# CCM_0011_Subrack_Backplane.net
KiCad netlist of a schematic drawn in EAGLE
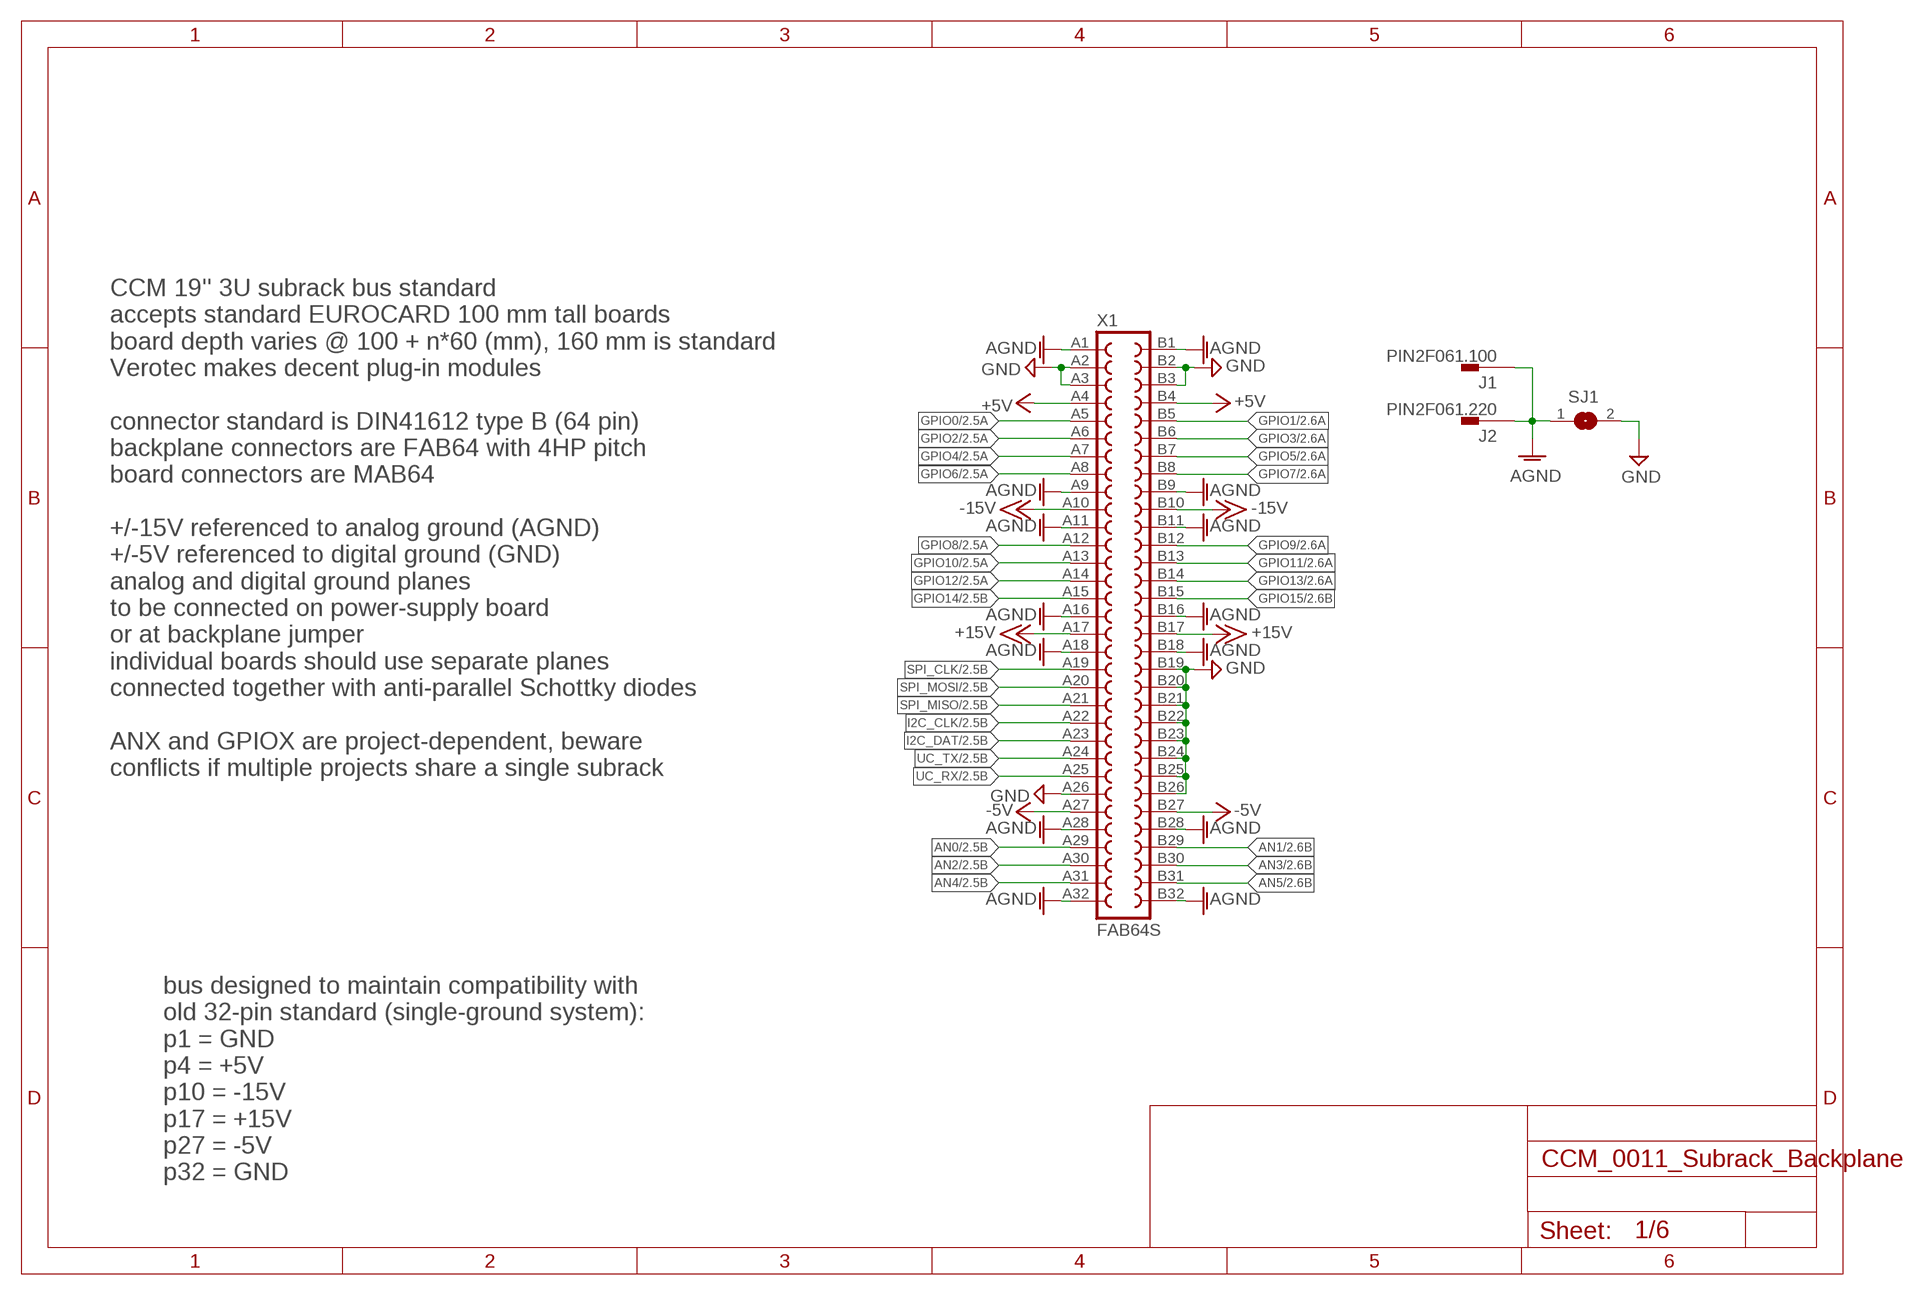
[diagram p0: schematic, sheet 1]
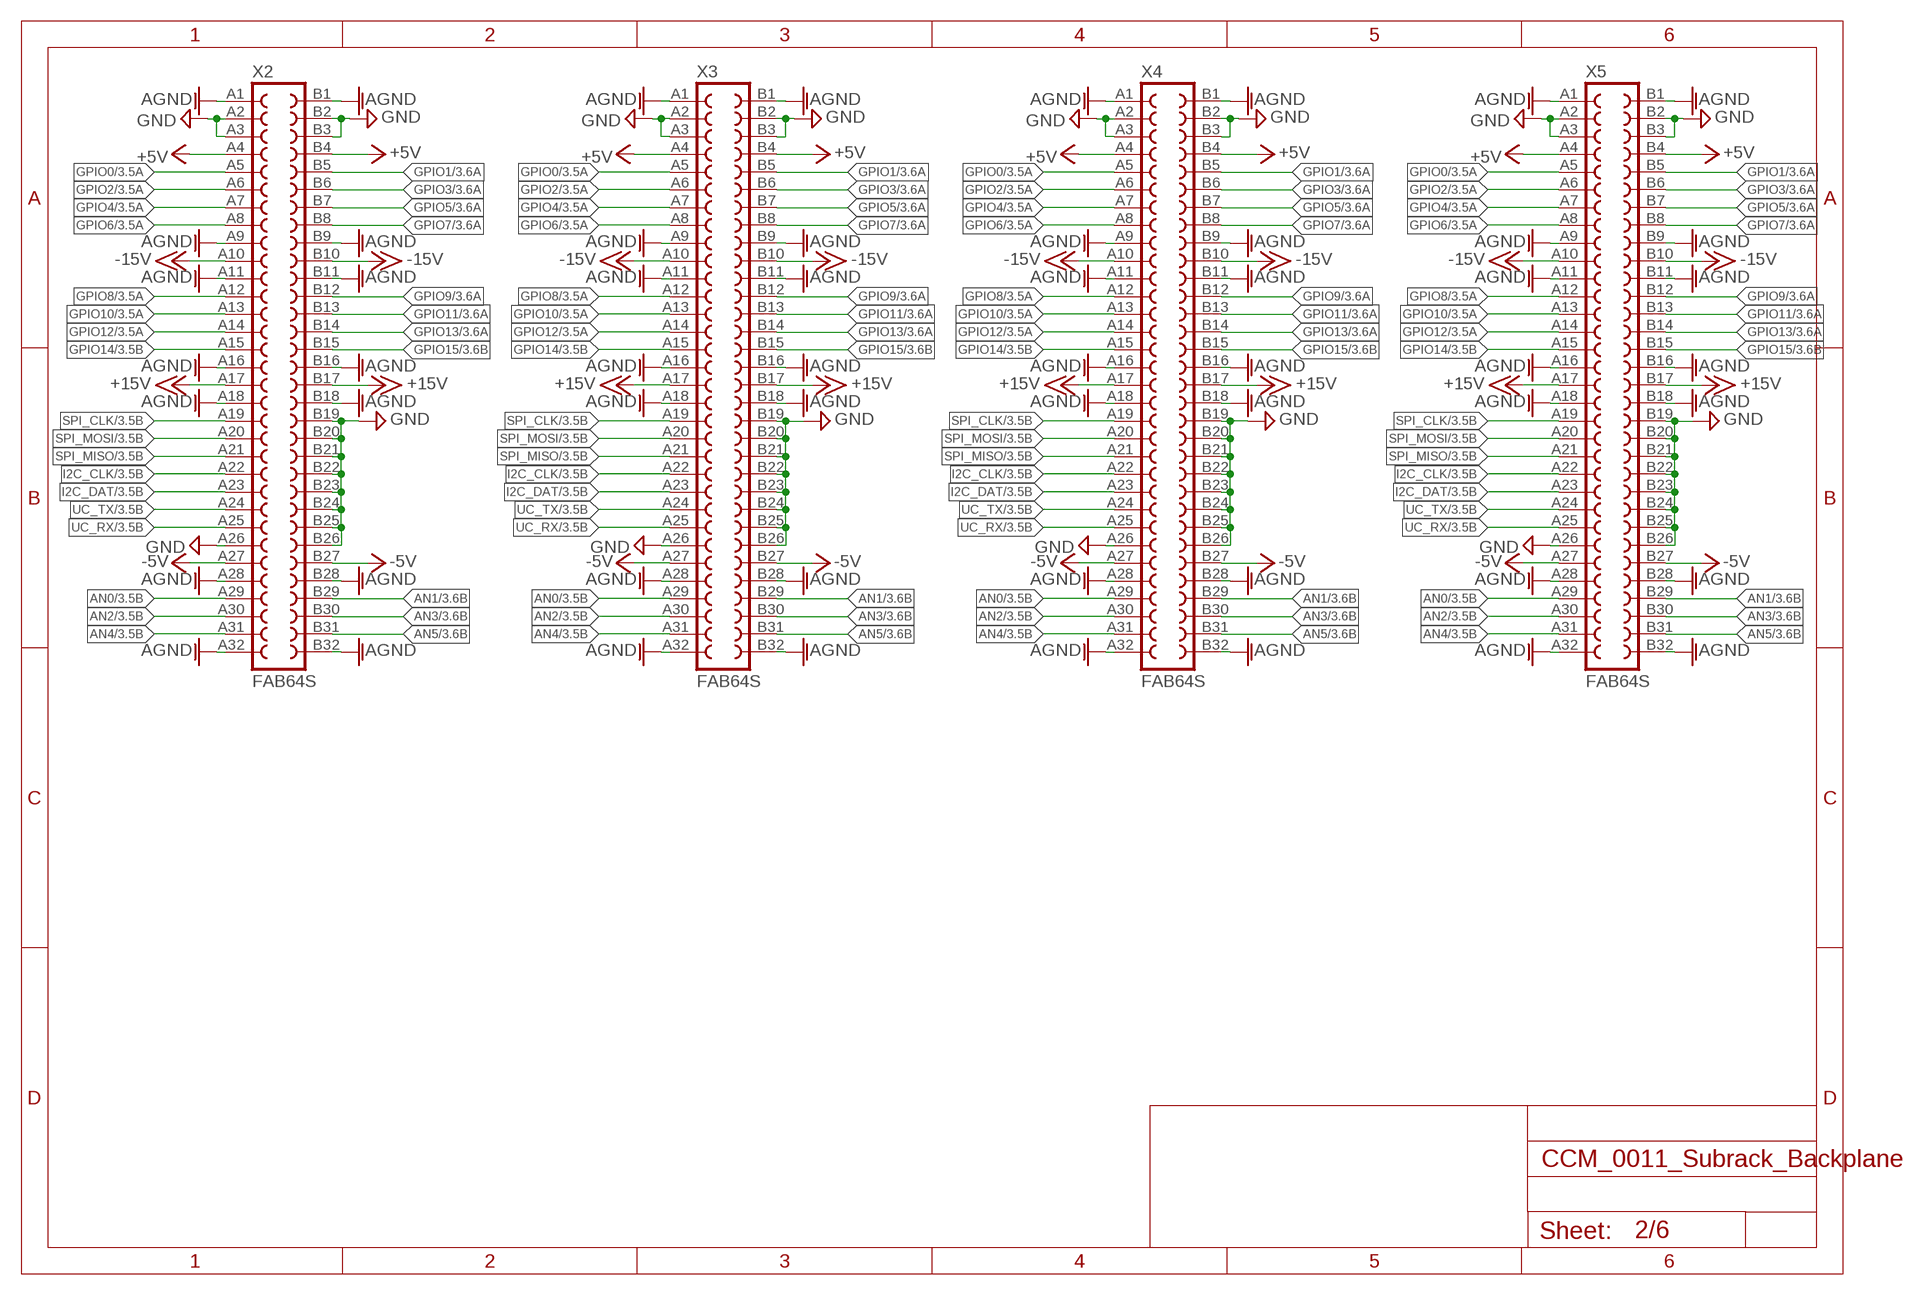
[diagram p1: schematic, sheet 2]
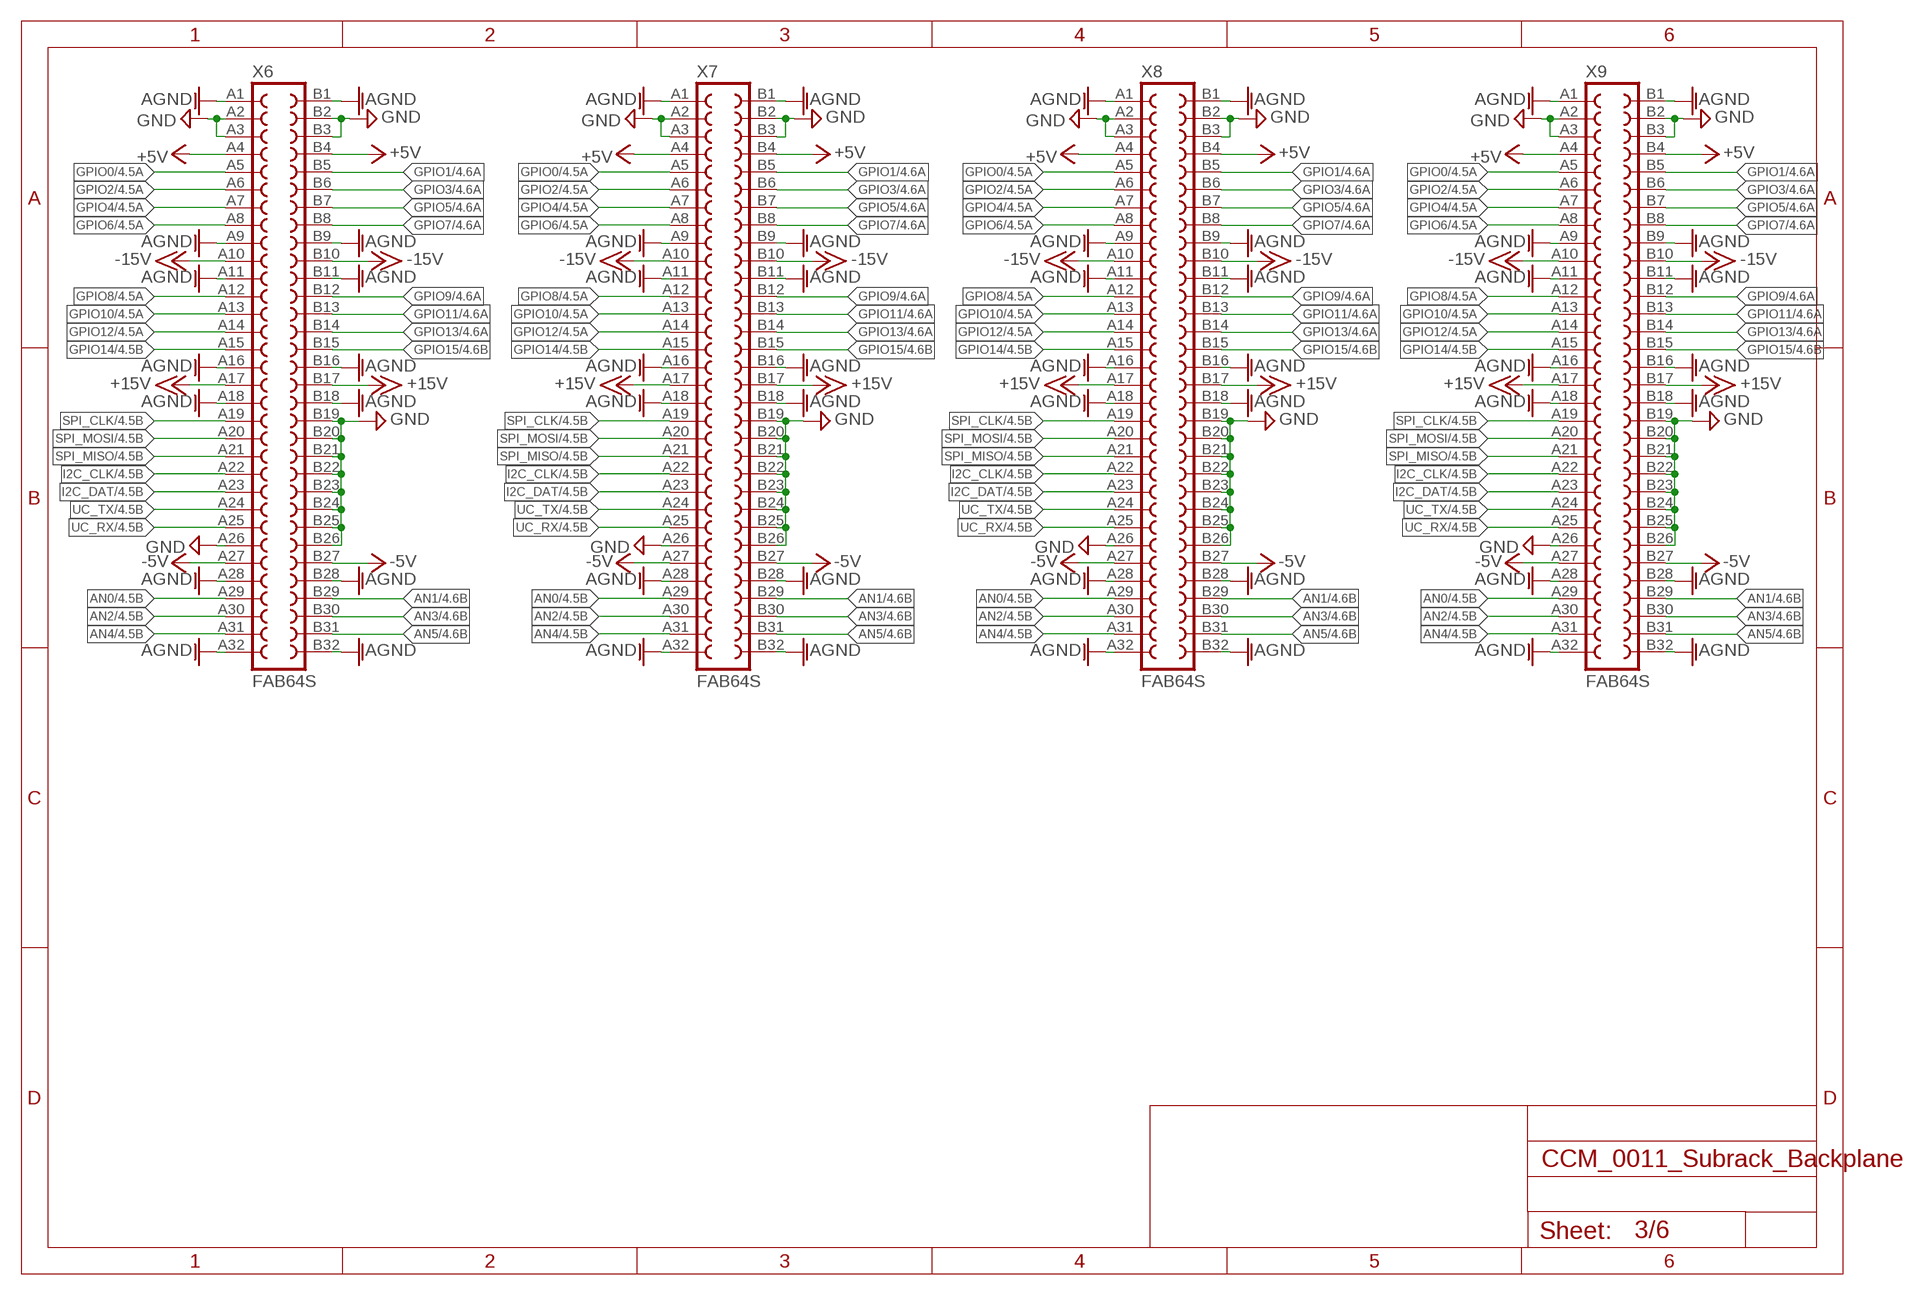
[diagram p2: schematic, sheet 3]
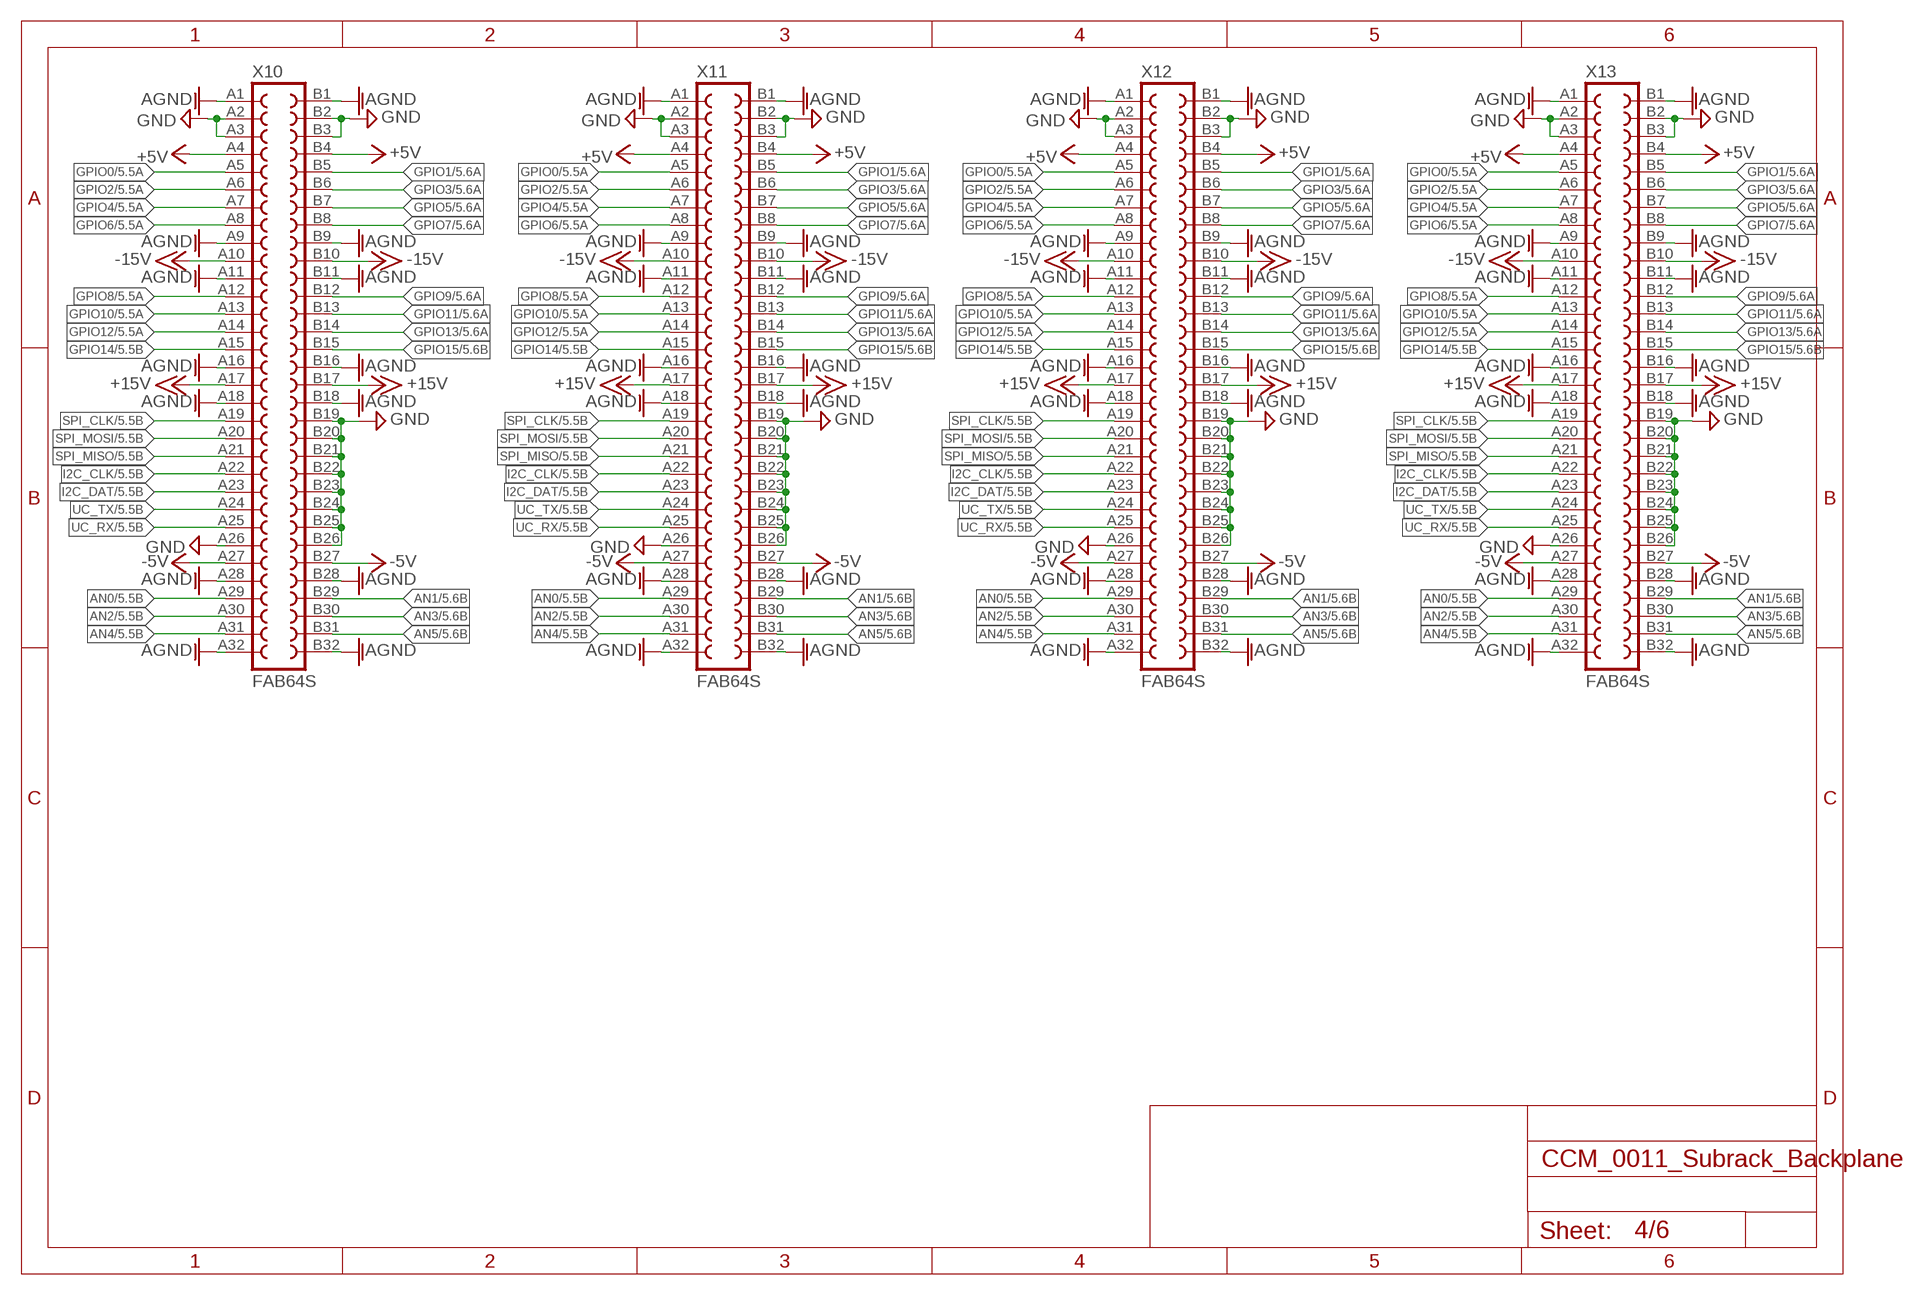
[diagram p3: schematic, sheet 4]
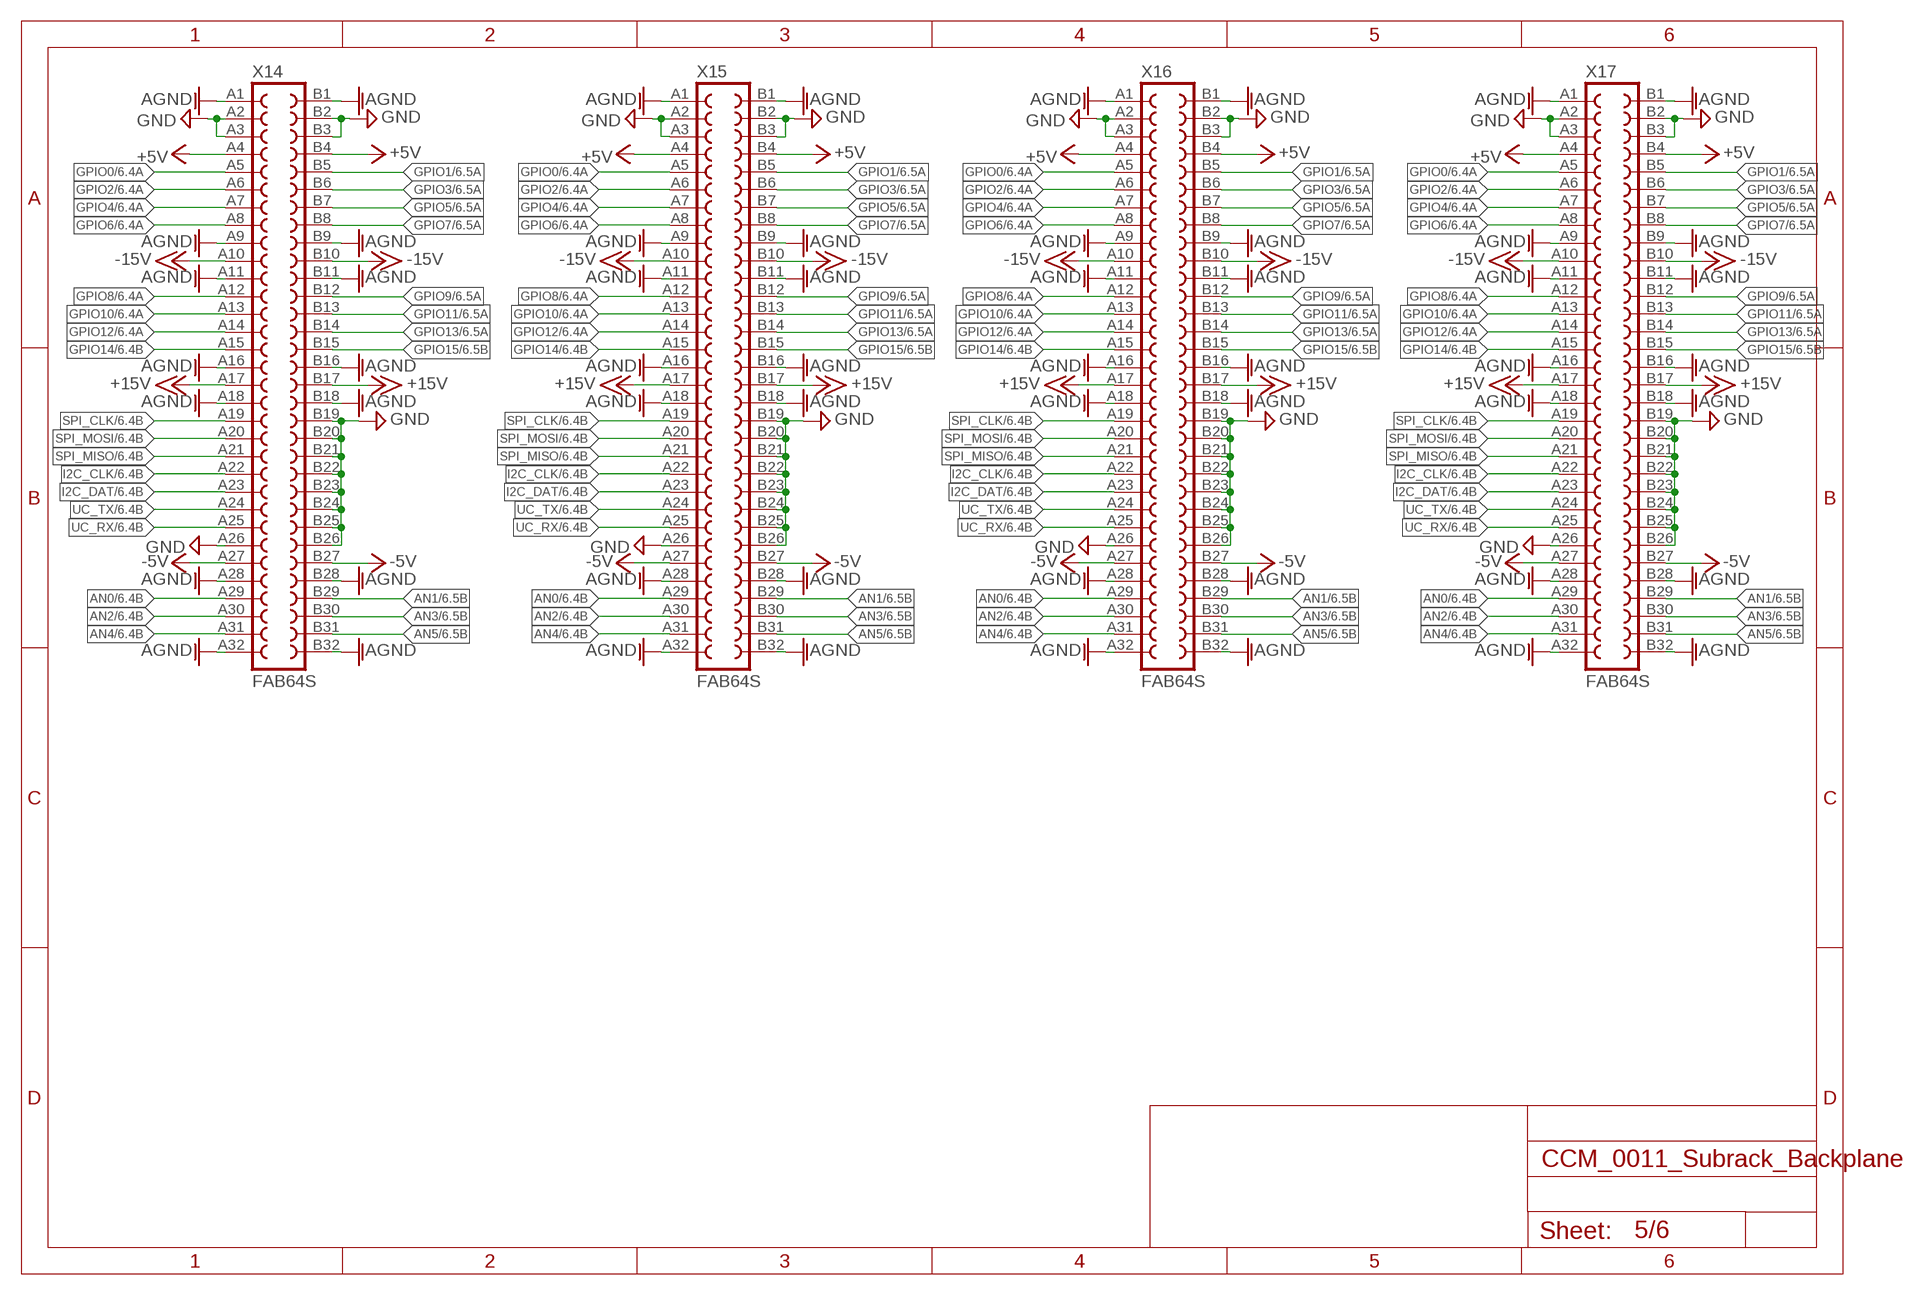
[diagram p4: schematic, sheet 5]
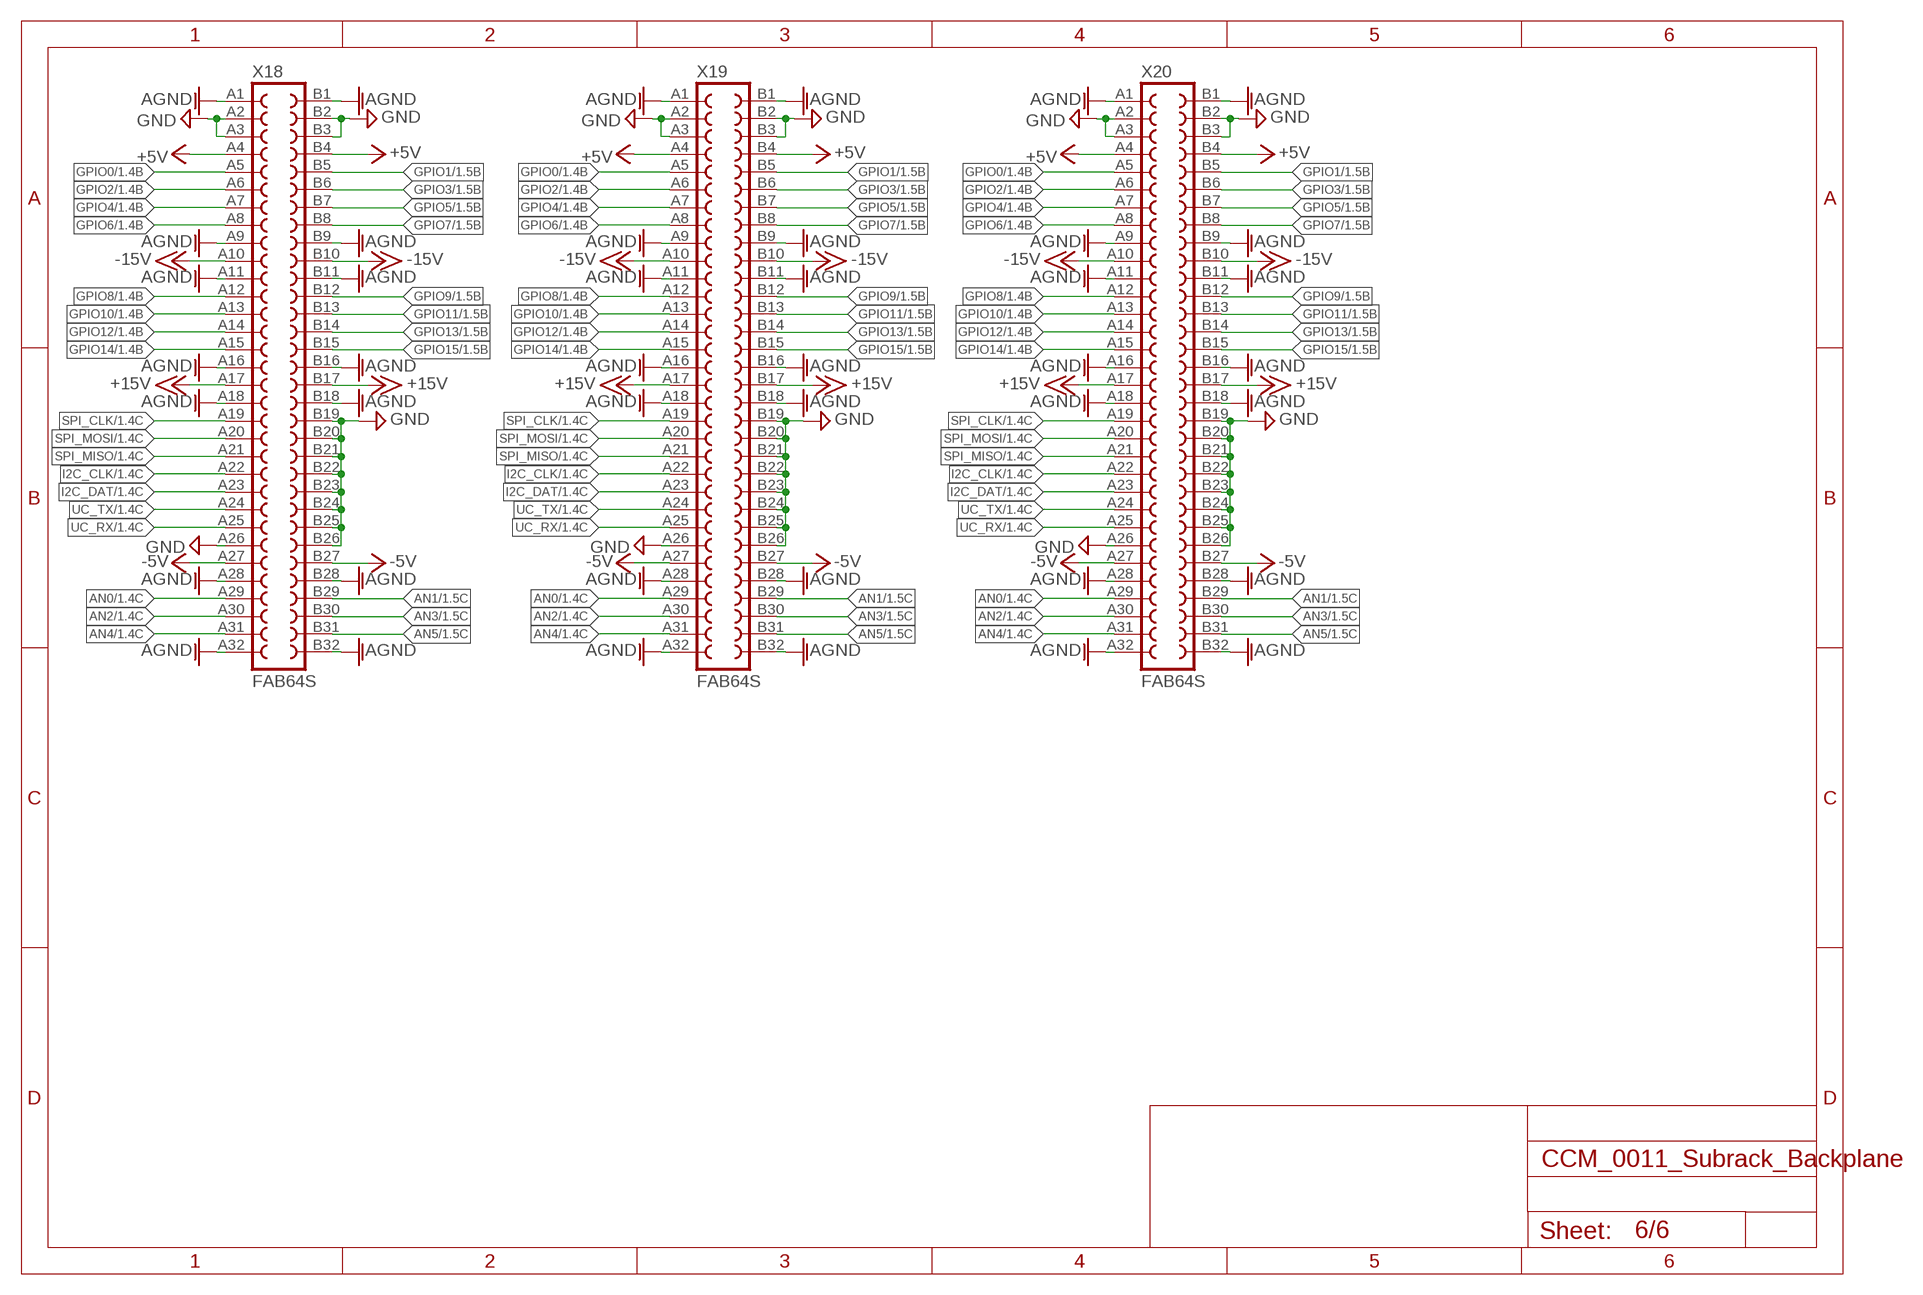
[diagram p5: schematic, sheet 6]

(export (version "E")
  (design (tool "Eeschema 10.0.6"))
  (components
    (comp (ref "X6")
      (value "FAB64S")
      (footprint "eagle-import:FAB64S")
      (libsource (lib "eagle-import") (part "FAB64S"))
    )
    (comp (ref "X7")
      (value "FAB64S")
      (footprint "eagle-import:FAB64S")
      (libsource (lib "eagle-import") (part "FAB64S"))
    )
    (comp (ref "X8")
      (value "FAB64S")
      (footprint "eagle-import:FAB64S")
      (libsource (lib "eagle-import") (part "FAB64S"))
    )
    (comp (ref "X9")
      (value "FAB64S")
      (footprint "eagle-import:FAB64S")
      (libsource (lib "eagle-import") (part "FAB64S"))
    )
    (comp (ref "X2")
      (value "FAB64S")
      (footprint "eagle-import:FAB64S")
      (libsource (lib "eagle-import") (part "FAB64S"))
    )
    (comp (ref "X3")
      (value "FAB64S")
      (footprint "eagle-import:FAB64S")
      (libsource (lib "eagle-import") (part "FAB64S"))
    )
    (comp (ref "X4")
      (value "FAB64S")
      (footprint "eagle-import:FAB64S")
      (libsource (lib "eagle-import") (part "FAB64S"))
    )
    (comp (ref "X5")
      (value "FAB64S")
      (footprint "eagle-import:FAB64S")
      (libsource (lib "eagle-import") (part "FAB64S"))
    )
    (comp (ref "J1")
      (value "PIN2F061.100")
      (footprint "eagle-import:F061.100")
      (libsource (lib "eagle-import") (part "PIN2F061.100"))
    )
    (comp (ref "J2")
      (value "PIN2F061.220")
      (footprint "eagle-import:F061.220")
      (libsource (lib "eagle-import") (part "PIN2F061.220"))
    )
    (comp (ref "SJ1") (value "SJ") (footprint "eagle-import:SJ") (libsource (lib "eagle-import") (part "SJ")))
    (comp (ref "X1")
      (value "FAB64S")
      (footprint "eagle-import:FAB64S")
      (libsource (lib "eagle-import") (part "noah_FAB64S"))
    )
    (comp (ref "X14")
      (value "FAB64S")
      (footprint "eagle-import:FAB64S")
      (libsource (lib "eagle-import") (part "FAB64S"))
    )
    (comp (ref "X15")
      (value "FAB64S")
      (footprint "eagle-import:FAB64S")
      (libsource (lib "eagle-import") (part "FAB64S"))
    )
    (comp (ref "X16")
      (value "FAB64S")
      (footprint "eagle-import:FAB64S")
      (libsource (lib "eagle-import") (part "FAB64S"))
    )
    (comp (ref "X17")
      (value "FAB64S")
      (footprint "eagle-import:FAB64S")
      (libsource (lib "eagle-import") (part "FAB64S"))
    )
    (comp (ref "X10")
      (value "FAB64S")
      (footprint "eagle-import:FAB64S")
      (libsource (lib "eagle-import") (part "FAB64S"))
    )
    (comp (ref "X11")
      (value "FAB64S")
      (footprint "eagle-import:FAB64S")
      (libsource (lib "eagle-import") (part "FAB64S"))
    )
    (comp (ref "X12")
      (value "FAB64S")
      (footprint "eagle-import:FAB64S")
      (libsource (lib "eagle-import") (part "FAB64S"))
    )
    (comp (ref "X13")
      (value "FAB64S")
      (footprint "eagle-import:FAB64S")
      (libsource (lib "eagle-import") (part "FAB64S"))
    )
    (comp (ref "X18")
      (value "FAB64S")
      (footprint "eagle-import:FAB64S")
      (libsource (lib "eagle-import") (part "FAB64S"))
    )
    (comp (ref "X19")
      (value "FAB64S")
      (footprint "eagle-import:FAB64S")
      (libsource (lib "eagle-import") (part "FAB64S"))
    )
    (comp (ref "X20")
      (value "FAB64S")
      (footprint "eagle-import:FAB64S")
      (libsource (lib "eagle-import") (part "FAB64S"))
    )
  )
  (nets
    (net (code "1") (name "+5V") (class "Default")
      (node (ref "X1") (pin "A4") (pinfunction "A4_A4") (pintype "passive"))
      (node (ref "X1") (pin "B4") (pinfunction "B4_B4") (pintype "passive"))
      (node (ref "X10") (pin "A4") (pinfunction "A4_A4") (pintype "passive"))
      (node (ref "X10") (pin "B4") (pinfunction "B4_B4") (pintype "passive"))
      (node (ref "X11") (pin "A4") (pinfunction "A4_A4") (pintype "passive"))
      (node (ref "X11") (pin "B4") (pinfunction "B4_B4") (pintype "passive"))
      (node (ref "X12") (pin "A4") (pinfunction "A4_A4") (pintype "passive"))
      (node (ref "X12") (pin "B4") (pinfunction "B4_B4") (pintype "passive"))
      (node (ref "X13") (pin "A4") (pinfunction "A4_A4") (pintype "passive"))
      (node (ref "X13") (pin "B4") (pinfunction "B4_B4") (pintype "passive"))
      (node (ref "X14") (pin "A4") (pinfunction "A4_A4") (pintype "passive"))
      (node (ref "X14") (pin "B4") (pinfunction "B4_B4") (pintype "passive"))
      (node (ref "X15") (pin "A4") (pinfunction "A4_A4") (pintype "passive"))
      (node (ref "X15") (pin "B4") (pinfunction "B4_B4") (pintype "passive"))
      (node (ref "X16") (pin "A4") (pinfunction "A4_A4") (pintype "passive"))
      (node (ref "X16") (pin "B4") (pinfunction "B4_B4") (pintype "passive"))
      (node (ref "X17") (pin "A4") (pinfunction "A4_A4") (pintype "passive"))
      (node (ref "X17") (pin "B4") (pinfunction "B4_B4") (pintype "passive"))
      (node (ref "X18") (pin "A4") (pinfunction "A4_A4") (pintype "passive"))
      (node (ref "X18") (pin "B4") (pinfunction "B4_B4") (pintype "passive"))
      (node (ref "X19") (pin "A4") (pinfunction "A4_A4") (pintype "passive"))
      (node (ref "X19") (pin "B4") (pinfunction "B4_B4") (pintype "passive"))
      (node (ref "X2") (pin "A4") (pinfunction "A4_A4") (pintype "passive"))
      (node (ref "X2") (pin "B4") (pinfunction "B4_B4") (pintype "passive"))
      (node (ref "X20") (pin "A4") (pinfunction "A4_A4") (pintype "passive"))
      (node (ref "X20") (pin "B4") (pinfunction "B4_B4") (pintype "passive"))
      (node (ref "X3") (pin "A4") (pinfunction "A4_A4") (pintype "passive"))
      (node (ref "X3") (pin "B4") (pinfunction "B4_B4") (pintype "passive"))
      (node (ref "X4") (pin "A4") (pinfunction "A4_A4") (pintype "passive"))
      (node (ref "X4") (pin "B4") (pinfunction "B4_B4") (pintype "passive"))
      (node (ref "X5") (pin "A4") (pinfunction "A4_A4") (pintype "passive"))
      (node (ref "X5") (pin "B4") (pinfunction "B4_B4") (pintype "passive"))
      (node (ref "X6") (pin "A4") (pinfunction "A4_A4") (pintype "passive"))
      (node (ref "X6") (pin "B4") (pinfunction "B4_B4") (pintype "passive"))
      (node (ref "X7") (pin "A4") (pinfunction "A4_A4") (pintype "passive"))
      (node (ref "X7") (pin "B4") (pinfunction "B4_B4") (pintype "passive"))
      (node (ref "X8") (pin "A4") (pinfunction "A4_A4") (pintype "passive"))
      (node (ref "X8") (pin "B4") (pinfunction "B4_B4") (pintype "passive"))
      (node (ref "X9") (pin "A4") (pinfunction "A4_A4") (pintype "passive"))
      (node (ref "X9") (pin "B4") (pinfunction "B4_B4") (pintype "passive"))
    )
    (net (code "2") (name "+15V") (class "Default")
      (node (ref "X1") (pin "A17") (pinfunction "A17_A17") (pintype "passive"))
      (node (ref "X1") (pin "B17") (pinfunction "B17_B17") (pintype "passive"))
      (node (ref "X10") (pin "A17") (pinfunction "A17_A17") (pintype "passive"))
      (node (ref "X10") (pin "B17") (pinfunction "B17_B17") (pintype "passive"))
      (node (ref "X11") (pin "A17") (pinfunction "A17_A17") (pintype "passive"))
      (node (ref "X11") (pin "B17") (pinfunction "B17_B17") (pintype "passive"))
      (node (ref "X12") (pin "A17") (pinfunction "A17_A17") (pintype "passive"))
      (node (ref "X12") (pin "B17") (pinfunction "B17_B17") (pintype "passive"))
      (node (ref "X13") (pin "A17") (pinfunction "A17_A17") (pintype "passive"))
      (node (ref "X13") (pin "B17") (pinfunction "B17_B17") (pintype "passive"))
      (node (ref "X14") (pin "A17") (pinfunction "A17_A17") (pintype "passive"))
      (node (ref "X14") (pin "B17") (pinfunction "B17_B17") (pintype "passive"))
      (node (ref "X15") (pin "A17") (pinfunction "A17_A17") (pintype "passive"))
      (node (ref "X15") (pin "B17") (pinfunction "B17_B17") (pintype "passive"))
      (node (ref "X16") (pin "A17") (pinfunction "A17_A17") (pintype "passive"))
      (node (ref "X16") (pin "B17") (pinfunction "B17_B17") (pintype "passive"))
      (node (ref "X17") (pin "A17") (pinfunction "A17_A17") (pintype "passive"))
      (node (ref "X17") (pin "B17") (pinfunction "B17_B17") (pintype "passive"))
      (node (ref "X18") (pin "A17") (pinfunction "A17_A17") (pintype "passive"))
      (node (ref "X18") (pin "B17") (pinfunction "B17_B17") (pintype "passive"))
      (node (ref "X19") (pin "A17") (pinfunction "A17_A17") (pintype "passive"))
      (node (ref "X19") (pin "B17") (pinfunction "B17_B17") (pintype "passive"))
      (node (ref "X2") (pin "A17") (pinfunction "A17_A17") (pintype "passive"))
      (node (ref "X2") (pin "B17") (pinfunction "B17_B17") (pintype "passive"))
      (node (ref "X20") (pin "A17") (pinfunction "A17_A17") (pintype "passive"))
      (node (ref "X20") (pin "B17") (pinfunction "B17_B17") (pintype "passive"))
      (node (ref "X3") (pin "A17") (pinfunction "A17_A17") (pintype "passive"))
      (node (ref "X3") (pin "B17") (pinfunction "B17_B17") (pintype "passive"))
      (node (ref "X4") (pin "A17") (pinfunction "A17_A17") (pintype "passive"))
      (node (ref "X4") (pin "B17") (pinfunction "B17_B17") (pintype "passive"))
      (node (ref "X5") (pin "A17") (pinfunction "A17_A17") (pintype "passive"))
      (node (ref "X5") (pin "B17") (pinfunction "B17_B17") (pintype "passive"))
      (node (ref "X6") (pin "A17") (pinfunction "A17_A17") (pintype "passive"))
      (node (ref "X6") (pin "B17") (pinfunction "B17_B17") (pintype "passive"))
      (node (ref "X7") (pin "A17") (pinfunction "A17_A17") (pintype "passive"))
      (node (ref "X7") (pin "B17") (pinfunction "B17_B17") (pintype "passive"))
      (node (ref "X8") (pin "A17") (pinfunction "A17_A17") (pintype "passive"))
      (node (ref "X8") (pin "B17") (pinfunction "B17_B17") (pintype "passive"))
      (node (ref "X9") (pin "A17") (pinfunction "A17_A17") (pintype "passive"))
      (node (ref "X9") (pin "B17") (pinfunction "B17_B17") (pintype "passive"))
    )
    (net (code "3") (name "-5V") (class "Default")
      (node (ref "X1") (pin "A27") (pinfunction "A27_A27") (pintype "passive"))
      (node (ref "X1") (pin "B27") (pinfunction "B27_B27") (pintype "passive"))
      (node (ref "X10") (pin "A27") (pinfunction "A27_A27") (pintype "passive"))
      (node (ref "X10") (pin "B27") (pinfunction "B27_B27") (pintype "passive"))
      (node (ref "X11") (pin "A27") (pinfunction "A27_A27") (pintype "passive"))
      (node (ref "X11") (pin "B27") (pinfunction "B27_B27") (pintype "passive"))
      (node (ref "X12") (pin "A27") (pinfunction "A27_A27") (pintype "passive"))
      (node (ref "X12") (pin "B27") (pinfunction "B27_B27") (pintype "passive"))
      (node (ref "X13") (pin "A27") (pinfunction "A27_A27") (pintype "passive"))
      (node (ref "X13") (pin "B27") (pinfunction "B27_B27") (pintype "passive"))
      (node (ref "X14") (pin "A27") (pinfunction "A27_A27") (pintype "passive"))
      (node (ref "X14") (pin "B27") (pinfunction "B27_B27") (pintype "passive"))
      (node (ref "X15") (pin "A27") (pinfunction "A27_A27") (pintype "passive"))
      (node (ref "X15") (pin "B27") (pinfunction "B27_B27") (pintype "passive"))
      (node (ref "X16") (pin "A27") (pinfunction "A27_A27") (pintype "passive"))
      (node (ref "X16") (pin "B27") (pinfunction "B27_B27") (pintype "passive"))
      (node (ref "X17") (pin "A27") (pinfunction "A27_A27") (pintype "passive"))
      (node (ref "X17") (pin "B27") (pinfunction "B27_B27") (pintype "passive"))
      (node (ref "X18") (pin "A27") (pinfunction "A27_A27") (pintype "passive"))
      (node (ref "X18") (pin "B27") (pinfunction "B27_B27") (pintype "passive"))
      (node (ref "X19") (pin "A27") (pinfunction "A27_A27") (pintype "passive"))
      (node (ref "X19") (pin "B27") (pinfunction "B27_B27") (pintype "passive"))
      (node (ref "X2") (pin "A27") (pinfunction "A27_A27") (pintype "passive"))
      (node (ref "X2") (pin "B27") (pinfunction "B27_B27") (pintype "passive"))
      (node (ref "X20") (pin "A27") (pinfunction "A27_A27") (pintype "passive"))
      (node (ref "X20") (pin "B27") (pinfunction "B27_B27") (pintype "passive"))
      (node (ref "X3") (pin "A27") (pinfunction "A27_A27") (pintype "passive"))
      (node (ref "X3") (pin "B27") (pinfunction "B27_B27") (pintype "passive"))
      (node (ref "X4") (pin "A27") (pinfunction "A27_A27") (pintype "passive"))
      (node (ref "X4") (pin "B27") (pinfunction "B27_B27") (pintype "passive"))
      (node (ref "X5") (pin "A27") (pinfunction "A27_A27") (pintype "passive"))
      (node (ref "X5") (pin "B27") (pinfunction "B27_B27") (pintype "passive"))
      (node (ref "X6") (pin "A27") (pinfunction "A27_A27") (pintype "passive"))
      (node (ref "X6") (pin "B27") (pinfunction "B27_B27") (pintype "passive"))
      (node (ref "X7") (pin "A27") (pinfunction "A27_A27") (pintype "passive"))
      (node (ref "X7") (pin "B27") (pinfunction "B27_B27") (pintype "passive"))
      (node (ref "X8") (pin "A27") (pinfunction "A27_A27") (pintype "passive"))
      (node (ref "X8") (pin "B27") (pinfunction "B27_B27") (pintype "passive"))
      (node (ref "X9") (pin "A27") (pinfunction "A27_A27") (pintype "passive"))
      (node (ref "X9") (pin "B27") (pinfunction "B27_B27") (pintype "passive"))
    )
    (net (code "4") (name "-15V") (class "Default")
      (node (ref "X1") (pin "A10") (pinfunction "A10_A10") (pintype "passive"))
      (node (ref "X1") (pin "B10") (pinfunction "B10_B10") (pintype "passive"))
      (node (ref "X10") (pin "A10") (pinfunction "A10_A10") (pintype "passive"))
      (node (ref "X10") (pin "B10") (pinfunction "B10_B10") (pintype "passive"))
      (node (ref "X11") (pin "A10") (pinfunction "A10_A10") (pintype "passive"))
      (node (ref "X11") (pin "B10") (pinfunction "B10_B10") (pintype "passive"))
      (node (ref "X12") (pin "A10") (pinfunction "A10_A10") (pintype "passive"))
      (node (ref "X12") (pin "B10") (pinfunction "B10_B10") (pintype "passive"))
      (node (ref "X13") (pin "A10") (pinfunction "A10_A10") (pintype "passive"))
      (node (ref "X13") (pin "B10") (pinfunction "B10_B10") (pintype "passive"))
      (node (ref "X14") (pin "A10") (pinfunction "A10_A10") (pintype "passive"))
      (node (ref "X14") (pin "B10") (pinfunction "B10_B10") (pintype "passive"))
      (node (ref "X15") (pin "A10") (pinfunction "A10_A10") (pintype "passive"))
      (node (ref "X15") (pin "B10") (pinfunction "B10_B10") (pintype "passive"))
      (node (ref "X16") (pin "A10") (pinfunction "A10_A10") (pintype "passive"))
      (node (ref "X16") (pin "B10") (pinfunction "B10_B10") (pintype "passive"))
      (node (ref "X17") (pin "A10") (pinfunction "A10_A10") (pintype "passive"))
      (node (ref "X17") (pin "B10") (pinfunction "B10_B10") (pintype "passive"))
      (node (ref "X18") (pin "A10") (pinfunction "A10_A10") (pintype "passive"))
      (node (ref "X18") (pin "B10") (pinfunction "B10_B10") (pintype "passive"))
      (node (ref "X19") (pin "A10") (pinfunction "A10_A10") (pintype "passive"))
      (node (ref "X19") (pin "B10") (pinfunction "B10_B10") (pintype "passive"))
      (node (ref "X2") (pin "A10") (pinfunction "A10_A10") (pintype "passive"))
      (node (ref "X2") (pin "B10") (pinfunction "B10_B10") (pintype "passive"))
      (node (ref "X20") (pin "A10") (pinfunction "A10_A10") (pintype "passive"))
      (node (ref "X20") (pin "B10") (pinfunction "B10_B10") (pintype "passive"))
      (node (ref "X3") (pin "A10") (pinfunction "A10_A10") (pintype "passive"))
      (node (ref "X3") (pin "B10") (pinfunction "B10_B10") (pintype "passive"))
      (node (ref "X4") (pin "A10") (pinfunction "A10_A10") (pintype "passive"))
      (node (ref "X4") (pin "B10") (pinfunction "B10_B10") (pintype "passive"))
      (node (ref "X5") (pin "A10") (pinfunction "A10_A10") (pintype "passive"))
      (node (ref "X5") (pin "B10") (pinfunction "B10_B10") (pintype "passive"))
      (node (ref "X6") (pin "A10") (pinfunction "A10_A10") (pintype "passive"))
      (node (ref "X6") (pin "B10") (pinfunction "B10_B10") (pintype "passive"))
      (node (ref "X7") (pin "A10") (pinfunction "A10_A10") (pintype "passive"))
      (node (ref "X7") (pin "B10") (pinfunction "B10_B10") (pintype "passive"))
      (node (ref "X8") (pin "A10") (pinfunction "A10_A10") (pintype "passive"))
      (node (ref "X8") (pin "B10") (pinfunction "B10_B10") (pintype "passive"))
      (node (ref "X9") (pin "A10") (pinfunction "A10_A10") (pintype "passive"))
      (node (ref "X9") (pin "B10") (pinfunction "B10_B10") (pintype "passive"))
    )
    (net (code "5") (name "AGND") (class "Default")
      (node (ref "J1") (pin "A1") (pinfunction "1_A1") (pintype "passive"))
      (node (ref "J1") (pin "A2") (pinfunction "1_A2") (pintype "passive"))
      (node (ref "J2") (pin "1A") (pinfunction "1_1A") (pintype "passive"))
      (node (ref "J2") (pin "1B") (pinfunction "1_1B") (pintype "passive"))
      (node (ref "SJ1") (pin "1") (pinfunction "1_1") (pintype "passive"))
      (node (ref "X1") (pin "A1") (pinfunction "A1_A1") (pintype "passive"))
      (node (ref "X1") (pin "A11") (pinfunction "A11_A11") (pintype "passive"))
      (node (ref "X1") (pin "A16") (pinfunction "A16_A16") (pintype "passive"))
      (node (ref "X1") (pin "A18") (pinfunction "A18_A18") (pintype "passive"))
      (node (ref "X1") (pin "A28") (pinfunction "A28_A28") (pintype "passive"))
      (node (ref "X1") (pin "A32") (pinfunction "A32_A32") (pintype "passive"))
      (node (ref "X1") (pin "A9") (pinfunction "A9_A9") (pintype "passive"))
      (node (ref "X1") (pin "B1") (pinfunction "B1_B1") (pintype "passive"))
      (node (ref "X1") (pin "B11") (pinfunction "B11_B11") (pintype "passive"))
      (node (ref "X1") (pin "B16") (pinfunction "B16_B16") (pintype "passive"))
      (node (ref "X1") (pin "B18") (pinfunction "B18_B18") (pintype "passive"))
      (node (ref "X1") (pin "B28") (pinfunction "B28_B28") (pintype "passive"))
      (node (ref "X1") (pin "B32") (pinfunction "B32_B32") (pintype "passive"))
      (node (ref "X1") (pin "B9") (pinfunction "B9_B9") (pintype "passive"))
      (node (ref "X10") (pin "A1") (pinfunction "A1_A1") (pintype "passive"))
      (node (ref "X10") (pin "A11") (pinfunction "A11_A11") (pintype "passive"))
      (node (ref "X10") (pin "A16") (pinfunction "A16_A16") (pintype "passive"))
      (node (ref "X10") (pin "A18") (pinfunction "A18_A18") (pintype "passive"))
      (node (ref "X10") (pin "A28") (pinfunction "A28_A28") (pintype "passive"))
      (node (ref "X10") (pin "A32") (pinfunction "A32_A32") (pintype "passive"))
      (node (ref "X10") (pin "A9") (pinfunction "A9_A9") (pintype "passive"))
      (node (ref "X10") (pin "B1") (pinfunction "B1_B1") (pintype "passive"))
      (node (ref "X10") (pin "B11") (pinfunction "B11_B11") (pintype "passive"))
      (node (ref "X10") (pin "B16") (pinfunction "B16_B16") (pintype "passive"))
      (node (ref "X10") (pin "B18") (pinfunction "B18_B18") (pintype "passive"))
      (node (ref "X10") (pin "B28") (pinfunction "B28_B28") (pintype "passive"))
      (node (ref "X10") (pin "B32") (pinfunction "B32_B32") (pintype "passive"))
      (node (ref "X10") (pin "B9") (pinfunction "B9_B9") (pintype "passive"))
      (node (ref "X11") (pin "A1") (pinfunction "A1_A1") (pintype "passive"))
      (node (ref "X11") (pin "A11") (pinfunction "A11_A11") (pintype "passive"))
      (node (ref "X11") (pin "A16") (pinfunction "A16_A16") (pintype "passive"))
      (node (ref "X11") (pin "A18") (pinfunction "A18_A18") (pintype "passive"))
      (node (ref "X11") (pin "A28") (pinfunction "A28_A28") (pintype "passive"))
      (node (ref "X11") (pin "A32") (pinfunction "A32_A32") (pintype "passive"))
      (node (ref "X11") (pin "A9") (pinfunction "A9_A9") (pintype "passive"))
      (node (ref "X11") (pin "B1") (pinfunction "B1_B1") (pintype "passive"))
      (node (ref "X11") (pin "B11") (pinfunction "B11_B11") (pintype "passive"))
      (node (ref "X11") (pin "B16") (pinfunction "B16_B16") (pintype "passive"))
      (node (ref "X11") (pin "B18") (pinfunction "B18_B18") (pintype "passive"))
      (node (ref "X11") (pin "B28") (pinfunction "B28_B28") (pintype "passive"))
      (node (ref "X11") (pin "B32") (pinfunction "B32_B32") (pintype "passive"))
      (node (ref "X11") (pin "B9") (pinfunction "B9_B9") (pintype "passive"))
      (node (ref "X12") (pin "A1") (pinfunction "A1_A1") (pintype "passive"))
      (node (ref "X12") (pin "A11") (pinfunction "A11_A11") (pintype "passive"))
      (node (ref "X12") (pin "A16") (pinfunction "A16_A16") (pintype "passive"))
      (node (ref "X12") (pin "A18") (pinfunction "A18_A18") (pintype "passive"))
      (node (ref "X12") (pin "A28") (pinfunction "A28_A28") (pintype "passive"))
      (node (ref "X12") (pin "A32") (pinfunction "A32_A32") (pintype "passive"))
      (node (ref "X12") (pin "A9") (pinfunction "A9_A9") (pintype "passive"))
      (node (ref "X12") (pin "B1") (pinfunction "B1_B1") (pintype "passive"))
      (node (ref "X12") (pin "B11") (pinfunction "B11_B11") (pintype "passive"))
      (node (ref "X12") (pin "B16") (pinfunction "B16_B16") (pintype "passive"))
      (node (ref "X12") (pin "B18") (pinfunction "B18_B18") (pintype "passive"))
      (node (ref "X12") (pin "B28") (pinfunction "B28_B28") (pintype "passive"))
      (node (ref "X12") (pin "B32") (pinfunction "B32_B32") (pintype "passive"))
      (node (ref "X12") (pin "B9") (pinfunction "B9_B9") (pintype "passive"))
      (node (ref "X13") (pin "A1") (pinfunction "A1_A1") (pintype "passive"))
      (node (ref "X13") (pin "A11") (pinfunction "A11_A11") (pintype "passive"))
      (node (ref "X13") (pin "A16") (pinfunction "A16_A16") (pintype "passive"))
      (node (ref "X13") (pin "A18") (pinfunction "A18_A18") (pintype "passive"))
      (node (ref "X13") (pin "A28") (pinfunction "A28_A28") (pintype "passive"))
      (node (ref "X13") (pin "A32") (pinfunction "A32_A32") (pintype "passive"))
      (node (ref "X13") (pin "A9") (pinfunction "A9_A9") (pintype "passive"))
      (node (ref "X13") (pin "B1") (pinfunction "B1_B1") (pintype "passive"))
      (node (ref "X13") (pin "B11") (pinfunction "B11_B11") (pintype "passive"))
      (node (ref "X13") (pin "B16") (pinfunction "B16_B16") (pintype "passive"))
      (node (ref "X13") (pin "B18") (pinfunction "B18_B18") (pintype "passive"))
      (node (ref "X13") (pin "B28") (pinfunction "B28_B28") (pintype "passive"))
      (node (ref "X13") (pin "B32") (pinfunction "B32_B32") (pintype "passive"))
      (node (ref "X13") (pin "B9") (pinfunction "B9_B9") (pintype "passive"))
      (node (ref "X14") (pin "A1") (pinfunction "A1_A1") (pintype "passive"))
      (node (ref "X14") (pin "A11") (pinfunction "A11_A11") (pintype "passive"))
      (node (ref "X14") (pin "A16") (pinfunction "A16_A16") (pintype "passive"))
      (node (ref "X14") (pin "A18") (pinfunction "A18_A18") (pintype "passive"))
      (node (ref "X14") (pin "A28") (pinfunction "A28_A28") (pintype "passive"))
      (node (ref "X14") (pin "A32") (pinfunction "A32_A32") (pintype "passive"))
      (node (ref "X14") (pin "A9") (pinfunction "A9_A9") (pintype "passive"))
      (node (ref "X14") (pin "B1") (pinfunction "B1_B1") (pintype "passive"))
      (node (ref "X14") (pin "B11") (pinfunction "B11_B11") (pintype "passive"))
      (node (ref "X14") (pin "B16") (pinfunction "B16_B16") (pintype "passive"))
      (node (ref "X14") (pin "B18") (pinfunction "B18_B18") (pintype "passive"))
      (node (ref "X14") (pin "B28") (pinfunction "B28_B28") (pintype "passive"))
      (node (ref "X14") (pin "B32") (pinfunction "B32_B32") (pintype "passive"))
      (node (ref "X14") (pin "B9") (pinfunction "B9_B9") (pintype "passive"))
      (node (ref "X15") (pin "A1") (pinfunction "A1_A1") (pintype "passive"))
      (node (ref "X15") (pin "A11") (pinfunction "A11_A11") (pintype "passive"))
      (node (ref "X15") (pin "A16") (pinfunction "A16_A16") (pintype "passive"))
      (node (ref "X15") (pin "A18") (pinfunction "A18_A18") (pintype "passive"))
      (node (ref "X15") (pin "A28") (pinfunction "A28_A28") (pintype "passive"))
      (node (ref "X15") (pin "A32") (pinfunction "A32_A32") (pintype "passive"))
      (node (ref "X15") (pin "A9") (pinfunction "A9_A9") (pintype "passive"))
      (node (ref "X15") (pin "B1") (pinfunction "B1_B1") (pintype "passive"))
      (node (ref "X15") (pin "B11") (pinfunction "B11_B11") (pintype "passive"))
      (node (ref "X15") (pin "B16") (pinfunction "B16_B16") (pintype "passive"))
      (node (ref "X15") (pin "B18") (pinfunction "B18_B18") (pintype "passive"))
      (node (ref "X15") (pin "B28") (pinfunction "B28_B28") (pintype "passive"))
      (node (ref "X15") (pin "B32") (pinfunction "B32_B32") (pintype "passive"))
      (node (ref "X15") (pin "B9") (pinfunction "B9_B9") (pintype "passive"))
      (node (ref "X16") (pin "A1") (pinfunction "A1_A1") (pintype "passive"))
      (node (ref "X16") (pin "A11") (pinfunction "A11_A11") (pintype "passive"))
      (node (ref "X16") (pin "A16") (pinfunction "A16_A16") (pintype "passive"))
      (node (ref "X16") (pin "A18") (pinfunction "A18_A18") (pintype "passive"))
      (node (ref "X16") (pin "A28") (pinfunction "A28_A28") (pintype "passive"))
      (node (ref "X16") (pin "A32") (pinfunction "A32_A32") (pintype "passive"))
      (node (ref "X16") (pin "A9") (pinfunction "A9_A9") (pintype "passive"))
      (node (ref "X16") (pin "B1") (pinfunction "B1_B1") (pintype "passive"))
      (node (ref "X16") (pin "B11") (pinfunction "B11_B11") (pintype "passive"))
      (node (ref "X16") (pin "B16") (pinfunction "B16_B16") (pintype "passive"))
      (node (ref "X16") (pin "B18") (pinfunction "B18_B18") (pintype "passive"))
      (node (ref "X16") (pin "B28") (pinfunction "B28_B28") (pintype "passive"))
      (node (ref "X16") (pin "B32") (pinfunction "B32_B32") (pintype "passive"))
      (node (ref "X16") (pin "B9") (pinfunction "B9_B9") (pintype "passive"))
      (node (ref "X17") (pin "A1") (pinfunction "A1_A1") (pintype "passive"))
      (node (ref "X17") (pin "A11") (pinfunction "A11_A11") (pintype "passive"))
      (node (ref "X17") (pin "A16") (pinfunction "A16_A16") (pintype "passive"))
      (node (ref "X17") (pin "A18") (pinfunction "A18_A18") (pintype "passive"))
      (node (ref "X17") (pin "A28") (pinfunction "A28_A28") (pintype "passive"))
      (node (ref "X17") (pin "A32") (pinfunction "A32_A32") (pintype "passive"))
      (node (ref "X17") (pin "A9") (pinfunction "A9_A9") (pintype "passive"))
      (node (ref "X17") (pin "B1") (pinfunction "B1_B1") (pintype "passive"))
      (node (ref "X17") (pin "B11") (pinfunction "B11_B11") (pintype "passive"))
      (node (ref "X17") (pin "B16") (pinfunction "B16_B16") (pintype "passive"))
      (node (ref "X17") (pin "B18") (pinfunction "B18_B18") (pintype "passive"))
      (node (ref "X17") (pin "B28") (pinfunction "B28_B28") (pintype "passive"))
      (node (ref "X17") (pin "B32") (pinfunction "B32_B32") (pintype "passive"))
      (node (ref "X17") (pin "B9") (pinfunction "B9_B9") (pintype "passive"))
      (node (ref "X18") (pin "A1") (pinfunction "A1_A1") (pintype "passive"))
      (node (ref "X18") (pin "A11") (pinfunction "A11_A11") (pintype "passive"))
      (node (ref "X18") (pin "A16") (pinfunction "A16_A16") (pintype "passive"))
      (node (ref "X18") (pin "A18") (pinfunction "A18_A18") (pintype "passive"))
      (node (ref "X18") (pin "A28") (pinfunction "A28_A28") (pintype "passive"))
      (node (ref "X18") (pin "A32") (pinfunction "A32_A32") (pintype "passive"))
      (node (ref "X18") (pin "A9") (pinfunction "A9_A9") (pintype "passive"))
      (node (ref "X18") (pin "B1") (pinfunction "B1_B1") (pintype "passive"))
      (node (ref "X18") (pin "B11") (pinfunction "B11_B11") (pintype "passive"))
      (node (ref "X18") (pin "B16") (pinfunction "B16_B16") (pintype "passive"))
      (node (ref "X18") (pin "B18") (pinfunction "B18_B18") (pintype "passive"))
      (node (ref "X18") (pin "B28") (pinfunction "B28_B28") (pintype "passive"))
      (node (ref "X18") (pin "B32") (pinfunction "B32_B32") (pintype "passive"))
      (node (ref "X18") (pin "B9") (pinfunction "B9_B9") (pintype "passive"))
      (node (ref "X19") (pin "A1") (pinfunction "A1_A1") (pintype "passive"))
      (node (ref "X19") (pin "A11") (pinfunction "A11_A11") (pintype "passive"))
      (node (ref "X19") (pin "A16") (pinfunction "A16_A16") (pintype "passive"))
      (node (ref "X19") (pin "A18") (pinfunction "A18_A18") (pintype "passive"))
      (node (ref "X19") (pin "A28") (pinfunction "A28_A28") (pintype "passive"))
      (node (ref "X19") (pin "A32") (pinfunction "A32_A32") (pintype "passive"))
      (node (ref "X19") (pin "A9") (pinfunction "A9_A9") (pintype "passive"))
      (node (ref "X19") (pin "B1") (pinfunction "B1_B1") (pintype "passive"))
      (node (ref "X19") (pin "B11") (pinfunction "B11_B11") (pintype "passive"))
      (node (ref "X19") (pin "B16") (pinfunction "B16_B16") (pintype "passive"))
      (node (ref "X19") (pin "B18") (pinfunction "B18_B18") (pintype "passive"))
      (node (ref "X19") (pin "B28") (pinfunction "B28_B28") (pintype "passive"))
      (node (ref "X19") (pin "B32") (pinfunction "B32_B32") (pintype "passive"))
      (node (ref "X19") (pin "B9") (pinfunction "B9_B9") (pintype "passive"))
      (node (ref "X2") (pin "A1") (pinfunction "A1_A1") (pintype "passive"))
      (node (ref "X2") (pin "A11") (pinfunction "A11_A11") (pintype "passive"))
      (node (ref "X2") (pin "A16") (pinfunction "A16_A16") (pintype "passive"))
      (node (ref "X2") (pin "A18") (pinfunction "A18_A18") (pintype "passive"))
      (node (ref "X2") (pin "A28") (pinfunction "A28_A28") (pintype "passive"))
      (node (ref "X2") (pin "A32") (pinfunction "A32_A32") (pintype "passive"))
      (node (ref "X2") (pin "A9") (pinfunction "A9_A9") (pintype "passive"))
      (node (ref "X2") (pin "B1") (pinfunction "B1_B1") (pintype "passive"))
      (node (ref "X2") (pin "B11") (pinfunction "B11_B11") (pintype "passive"))
      (node (ref "X2") (pin "B16") (pinfunction "B16_B16") (pintype "passive"))
      (node (ref "X2") (pin "B18") (pinfunction "B18_B18") (pintype "passive"))
      (node (ref "X2") (pin "B28") (pinfunction "B28_B28") (pintype "passive"))
      (node (ref "X2") (pin "B32") (pinfunction "B32_B32") (pintype "passive"))
      (node (ref "X2") (pin "B9") (pinfunction "B9_B9") (pintype "passive"))
      (node (ref "X20") (pin "A1") (pinfunction "A1_A1") (pintype "passive"))
      (node (ref "X20") (pin "A11") (pinfunction "A11_A11") (pintype "passive"))
      (node (ref "X20") (pin "A16") (pinfunction "A16_A16") (pintype "passive"))
      (node (ref "X20") (pin "A18") (pinfunction "A18_A18") (pintype "passive"))
      (node (ref "X20") (pin "A28") (pinfunction "A28_A28") (pintype "passive"))
      (node (ref "X20") (pin "A32") (pinfunction "A32_A32") (pintype "passive"))
      (node (ref "X20") (pin "A9") (pinfunction "A9_A9") (pintype "passive"))
      (node (ref "X20") (pin "B1") (pinfunction "B1_B1") (pintype "passive"))
      (node (ref "X20") (pin "B11") (pinfunction "B11_B11") (pintype "passive"))
      (node (ref "X20") (pin "B16") (pinfunction "B16_B16") (pintype "passive"))
      (node (ref "X20") (pin "B18") (pinfunction "B18_B18") (pintype "passive"))
      (node (ref "X20") (pin "B28") (pinfunction "B28_B28") (pintype "passive"))
      (node (ref "X20") (pin "B32") (pinfunction "B32_B32") (pintype "passive"))
      (node (ref "X20") (pin "B9") (pinfunction "B9_B9") (pintype "passive"))
      (node (ref "X3") (pin "A1") (pinfunction "A1_A1") (pintype "passive"))
      (node (ref "X3") (pin "A11") (pinfunction "A11_A11") (pintype "passive"))
      (node (ref "X3") (pin "A16") (pinfunction "A16_A16") (pintype "passive"))
      (node (ref "X3") (pin "A18") (pinfunction "A18_A18") (pintype "passive"))
      (node (ref "X3") (pin "A28") (pinfunction "A28_A28") (pintype "passive"))
      (node (ref "X3") (pin "A32") (pinfunction "A32_A32") (pintype "passive"))
      (node (ref "X3") (pin "A9") (pinfunction "A9_A9") (pintype "passive"))
      (node (ref "X3") (pin "B1") (pinfunction "B1_B1") (pintype "passive"))
      (node (ref "X3") (pin "B11") (pinfunction "B11_B11") (pintype "passive"))
      (node (ref "X3") (pin "B16") (pinfunction "B16_B16") (pintype "passive"))
      (node (ref "X3") (pin "B18") (pinfunction "B18_B18") (pintype "passive"))
      (node (ref "X3") (pin "B28") (pinfunction "B28_B28") (pintype "passive"))
      (node (ref "X3") (pin "B32") (pinfunction "B32_B32") (pintype "passive"))
      (node (ref "X3") (pin "B9") (pinfunction "B9_B9") (pintype "passive"))
      (node (ref "X4") (pin "A1") (pinfunction "A1_A1") (pintype "passive"))
      (node (ref "X4") (pin "A11") (pinfunction "A11_A11") (pintype "passive"))
      (node (ref "X4") (pin "A16") (pinfunction "A16_A16") (pintype "passive"))
      (node (ref "X4") (pin "A18") (pinfunction "A18_A18") (pintype "passive"))
      (node (ref "X4") (pin "A28") (pinfunction "A28_A28") (pintype "passive"))
      (node (ref "X4") (pin "A32") (pinfunction "A32_A32") (pintype "passive"))
      (node (ref "X4") (pin "A9") (pinfunction "A9_A9") (pintype "passive"))
      (node (ref "X4") (pin "B1") (pinfunction "B1_B1") (pintype "passive"))
      (node (ref "X4") (pin "B11") (pinfunction "B11_B11") (pintype "passive"))
      (node (ref "X4") (pin "B16") (pinfunction "B16_B16") (pintype "passive"))
      (node (ref "X4") (pin "B18") (pinfunction "B18_B18") (pintype "passive"))
      (node (ref "X4") (pin "B28") (pinfunction "B28_B28") (pintype "passive"))
      (node (ref "X4") (pin "B32") (pinfunction "B32_B32") (pintype "passive"))
      (node (ref "X4") (pin "B9") (pinfunction "B9_B9") (pintype "passive"))
      (node (ref "X5") (pin "A1") (pinfunction "A1_A1") (pintype "passive"))
      (node (ref "X5") (pin "A11") (pinfunction "A11_A11") (pintype "passive"))
      (node (ref "X5") (pin "A16") (pinfunction "A16_A16") (pintype "passive"))
      (node (ref "X5") (pin "A18") (pinfunction "A18_A18") (pintype "passive"))
      (node (ref "X5") (pin "A28") (pinfunction "A28_A28") (pintype "passive"))
      (node (ref "X5") (pin "A32") (pinfunction "A32_A32") (pintype "passive"))
      (node (ref "X5") (pin "A9") (pinfunction "A9_A9") (pintype "passive"))
      (node (ref "X5") (pin "B1") (pinfunction "B1_B1") (pintype "passive"))
      (node (ref "X5") (pin "B11") (pinfunction "B11_B11") (pintype "passive"))
      (node (ref "X5") (pin "B16") (pinfunction "B16_B16") (pintype "passive"))
      (node (ref "X5") (pin "B18") (pinfunction "B18_B18") (pintype "passive"))
      (node (ref "X5") (pin "B28") (pinfunction "B28_B28") (pintype "passive"))
      (node (ref "X5") (pin "B32") (pinfunction "B32_B32") (pintype "passive"))
      (node (ref "X5") (pin "B9") (pinfunction "B9_B9") (pintype "passive"))
      (node (ref "X6") (pin "A1") (pinfunction "A1_A1") (pintype "passive"))
      (node (ref "X6") (pin "A11") (pinfunction "A11_A11") (pintype "passive"))
      (node (ref "X6") (pin "A16") (pinfunction "A16_A16") (pintype "passive"))
      (node (ref "X6") (pin "A18") (pinfunction "A18_A18") (pintype "passive"))
      (node (ref "X6") (pin "A28") (pinfunction "A28_A28") (pintype "passive"))
      (node (ref "X6") (pin "A32") (pinfunction "A32_A32") (pintype "passive"))
      (node (ref "X6") (pin "A9") (pinfunction "A9_A9") (pintype "passive"))
      (node (ref "X6") (pin "B1") (pinfunction "B1_B1") (pintype "passive"))
      (node (ref "X6") (pin "B11") (pinfunction "B11_B11") (pintype "passive"))
      (node (ref "X6") (pin "B16") (pinfunction "B16_B16") (pintype "passive"))
      (node (ref "X6") (pin "B18") (pinfunction "B18_B18") (pintype "passive"))
      (node (ref "X6") (pin "B28") (pinfunction "B28_B28") (pintype "passive"))
      (node (ref "X6") (pin "B32") (pinfunction "B32_B32") (pintype "passive"))
      (node (ref "X6") (pin "B9") (pinfunction "B9_B9") (pintype "passive"))
      (node (ref "X7") (pin "A1") (pinfunction "A1_A1") (pintype "passive"))
      (node (ref "X7") (pin "A11") (pinfunction "A11_A11") (pintype "passive"))
      (node (ref "X7") (pin "A16") (pinfunction "A16_A16") (pintype "passive"))
      (node (ref "X7") (pin "A18") (pinfunction "A18_A18") (pintype "passive"))
      (node (ref "X7") (pin "A28") (pinfunction "A28_A28") (pintype "passive"))
      (node (ref "X7") (pin "A32") (pinfunction "A32_A32") (pintype "passive"))
      (node (ref "X7") (pin "A9") (pinfunction "A9_A9") (pintype "passive"))
      (node (ref "X7") (pin "B1") (pinfunction "B1_B1") (pintype "passive"))
      (node (ref "X7") (pin "B11") (pinfunction "B11_B11") (pintype "passive"))
      (node (ref "X7") (pin "B16") (pinfunction "B16_B16") (pintype "passive"))
      (node (ref "X7") (pin "B18") (pinfunction "B18_B18") (pintype "passive"))
      (node (ref "X7") (pin "B28") (pinfunction "B28_B28") (pintype "passive"))
      (node (ref "X7") (pin "B32") (pinfunction "B32_B32") (pintype "passive"))
      (node (ref "X7") (pin "B9") (pinfunction "B9_B9") (pintype "passive"))
      (node (ref "X8") (pin "A1") (pinfunction "A1_A1") (pintype "passive"))
      (node (ref "X8") (pin "A11") (pinfunction "A11_A11") (pintype "passive"))
      (node (ref "X8") (pin "A16") (pinfunction "A16_A16") (pintype "passive"))
      (node (ref "X8") (pin "A18") (pinfunction "A18_A18") (pintype "passive"))
      (node (ref "X8") (pin "A28") (pinfunction "A28_A28") (pintype "passive"))
      (node (ref "X8") (pin "A32") (pinfunction "A32_A32") (pintype "passive"))
      (node (ref "X8") (pin "A9") (pinfunction "A9_A9") (pintype "passive"))
      (node (ref "X8") (pin "B1") (pinfunction "B1_B1") (pintype "passive"))
      (node (ref "X8") (pin "B11") (pinfunction "B11_B11") (pintype "passive"))
      (node (ref "X8") (pin "B16") (pinfunction "B16_B16") (pintype "passive"))
      (node (ref "X8") (pin "B18") (pinfunction "B18_B18") (pintype "passive"))
      (node (ref "X8") (pin "B28") (pinfunction "B28_B28") (pintype "passive"))
      (node (ref "X8") (pin "B32") (pinfunction "B32_B32") (pintype "passive"))
      (node (ref "X8") (pin "B9") (pinfunction "B9_B9") (pintype "passive"))
      (node (ref "X9") (pin "A1") (pinfunction "A1_A1") (pintype "passive"))
      (node (ref "X9") (pin "A11") (pinfunction "A11_A11") (pintype "passive"))
      (node (ref "X9") (pin "A16") (pinfunction "A16_A16") (pintype "passive"))
      (node (ref "X9") (pin "A18") (pinfunction "A18_A18") (pintype "passive"))
      (node (ref "X9") (pin "A28") (pinfunction "A28_A28") (pintype "passive"))
      (node (ref "X9") (pin "A32") (pinfunction "A32_A32") (pintype "passive"))
      (node (ref "X9") (pin "A9") (pinfunction "A9_A9") (pintype "passive"))
      (node (ref "X9") (pin "B1") (pinfunction "B1_B1") (pintype "passive"))
      (node (ref "X9") (pin "B11") (pinfunction "B11_B11") (pintype "passive"))
      (node (ref "X9") (pin "B16") (pinfunction "B16_B16") (pintype "passive"))
      (node (ref "X9") (pin "B18") (pinfunction "B18_B18") (pintype "passive"))
      (node (ref "X9") (pin "B28") (pinfunction "B28_B28") (pintype "passive"))
      (node (ref "X9") (pin "B32") (pinfunction "B32_B32") (pintype "passive"))
      (node (ref "X9") (pin "B9") (pinfunction "B9_B9") (pintype "passive"))
    )
    (net (code "6") (name "AN0") (class "Default")
      (node (ref "X1") (pin "A29") (pinfunction "A29_A29") (pintype "passive"))
      (node (ref "X10") (pin "A29") (pinfunction "A29_A29") (pintype "passive"))
      (node (ref "X11") (pin "A29") (pinfunction "A29_A29") (pintype "passive"))
      (node (ref "X12") (pin "A29") (pinfunction "A29_A29") (pintype "passive"))
      (node (ref "X13") (pin "A29") (pinfunction "A29_A29") (pintype "passive"))
      (node (ref "X14") (pin "A29") (pinfunction "A29_A29") (pintype "passive"))
      (node (ref "X15") (pin "A29") (pinfunction "A29_A29") (pintype "passive"))
      (node (ref "X16") (pin "A29") (pinfunction "A29_A29") (pintype "passive"))
      (node (ref "X17") (pin "A29") (pinfunction "A29_A29") (pintype "passive"))
      (node (ref "X18") (pin "A29") (pinfunction "A29_A29") (pintype "passive"))
      (node (ref "X19") (pin "A29") (pinfunction "A29_A29") (pintype "passive"))
      (node (ref "X2") (pin "A29") (pinfunction "A29_A29") (pintype "passive"))
      (node (ref "X20") (pin "A29") (pinfunction "A29_A29") (pintype "passive"))
      (node (ref "X3") (pin "A29") (pinfunction "A29_A29") (pintype "passive"))
      (node (ref "X4") (pin "A29") (pinfunction "A29_A29") (pintype "passive"))
      (node (ref "X5") (pin "A29") (pinfunction "A29_A29") (pintype "passive"))
      (node (ref "X6") (pin "A29") (pinfunction "A29_A29") (pintype "passive"))
      (node (ref "X7") (pin "A29") (pinfunction "A29_A29") (pintype "passive"))
      (node (ref "X8") (pin "A29") (pinfunction "A29_A29") (pintype "passive"))
      (node (ref "X9") (pin "A29") (pinfunction "A29_A29") (pintype "passive"))
    )
    (net (code "7") (name "AN1") (class "Default")
      (node (ref "X1") (pin "B29") (pinfunction "B29_B29") (pintype "passive"))
      (node (ref "X10") (pin "B29") (pinfunction "B29_B29") (pintype "passive"))
      (node (ref "X11") (pin "B29") (pinfunction "B29_B29") (pintype "passive"))
      (node (ref "X12") (pin "B29") (pinfunction "B29_B29") (pintype "passive"))
      (node (ref "X13") (pin "B29") (pinfunction "B29_B29") (pintype "passive"))
      (node (ref "X14") (pin "B29") (pinfunction "B29_B29") (pintype "passive"))
      (node (ref "X15") (pin "B29") (pinfunction "B29_B29") (pintype "passive"))
      (node (ref "X16") (pin "B29") (pinfunction "B29_B29") (pintype "passive"))
      (node (ref "X17") (pin "B29") (pinfunction "B29_B29") (pintype "passive"))
      (node (ref "X18") (pin "B29") (pinfunction "B29_B29") (pintype "passive"))
      (node (ref "X19") (pin "B29") (pinfunction "B29_B29") (pintype "passive"))
      (node (ref "X2") (pin "B29") (pinfunction "B29_B29") (pintype "passive"))
      (node (ref "X20") (pin "B29") (pinfunction "B29_B29") (pintype "passive"))
      (node (ref "X3") (pin "B29") (pinfunction "B29_B29") (pintype "passive"))
      (node (ref "X4") (pin "B29") (pinfunction "B29_B29") (pintype "passive"))
      (node (ref "X5") (pin "B29") (pinfunction "B29_B29") (pintype "passive"))
      (node (ref "X6") (pin "B29") (pinfunction "B29_B29") (pintype "passive"))
      (node (ref "X7") (pin "B29") (pinfunction "B29_B29") (pintype "passive"))
      (node (ref "X8") (pin "B29") (pinfunction "B29_B29") (pintype "passive"))
      (node (ref "X9") (pin "B29") (pinfunction "B29_B29") (pintype "passive"))
    )
    (net (code "8") (name "AN2") (class "Default")
      (node (ref "X1") (pin "A30") (pinfunction "A30_A30") (pintype "passive"))
      (node (ref "X10") (pin "A30") (pinfunction "A30_A30") (pintype "passive"))
      (node (ref "X11") (pin "A30") (pinfunction "A30_A30") (pintype "passive"))
      (node (ref "X12") (pin "A30") (pinfunction "A30_A30") (pintype "passive"))
      (node (ref "X13") (pin "A30") (pinfunction "A30_A30") (pintype "passive"))
      (node (ref "X14") (pin "A30") (pinfunction "A30_A30") (pintype "passive"))
      (node (ref "X15") (pin "A30") (pinfunction "A30_A30") (pintype "passive"))
      (node (ref "X16") (pin "A30") (pinfunction "A30_A30") (pintype "passive"))
      (node (ref "X17") (pin "A30") (pinfunction "A30_A30") (pintype "passive"))
      (node (ref "X18") (pin "A30") (pinfunction "A30_A30") (pintype "passive"))
      (node (ref "X19") (pin "A30") (pinfunction "A30_A30") (pintype "passive"))
      (node (ref "X2") (pin "A30") (pinfunction "A30_A30") (pintype "passive"))
      (node (ref "X20") (pin "A30") (pinfunction "A30_A30") (pintype "passive"))
      (node (ref "X3") (pin "A30") (pinfunction "A30_A30") (pintype "passive"))
      (node (ref "X4") (pin "A30") (pinfunction "A30_A30") (pintype "passive"))
      (node (ref "X5") (pin "A30") (pinfunction "A30_A30") (pintype "passive"))
      (node (ref "X6") (pin "A30") (pinfunction "A30_A30") (pintype "passive"))
      (node (ref "X7") (pin "A30") (pinfunction "A30_A30") (pintype "passive"))
      (node (ref "X8") (pin "A30") (pinfunction "A30_A30") (pintype "passive"))
      (node (ref "X9") (pin "A30") (pinfunction "A30_A30") (pintype "passive"))
    )
    (net (code "9") (name "AN3") (class "Default")
      (node (ref "X1") (pin "B30") (pinfunction "B30_B30") (pintype "passive"))
      (node (ref "X10") (pin "B30") (pinfunction "B30_B30") (pintype "passive"))
      (node (ref "X11") (pin "B30") (pinfunction "B30_B30") (pintype "passive"))
      (node (ref "X12") (pin "B30") (pinfunction "B30_B30") (pintype "passive"))
      (node (ref "X13") (pin "B30") (pinfunction "B30_B30") (pintype "passive"))
      (node (ref "X14") (pin "B30") (pinfunction "B30_B30") (pintype "passive"))
      (node (ref "X15") (pin "B30") (pinfunction "B30_B30") (pintype "passive"))
      (node (ref "X16") (pin "B30") (pinfunction "B30_B30") (pintype "passive"))
      (node (ref "X17") (pin "B30") (pinfunction "B30_B30") (pintype "passive"))
      (node (ref "X18") (pin "B30") (pinfunction "B30_B30") (pintype "passive"))
      (node (ref "X19") (pin "B30") (pinfunction "B30_B30") (pintype "passive"))
      (node (ref "X2") (pin "B30") (pinfunction "B30_B30") (pintype "passive"))
      (node (ref "X20") (pin "B30") (pinfunction "B30_B30") (pintype "passive"))
      (node (ref "X3") (pin "B30") (pinfunction "B30_B30") (pintype "passive"))
      (node (ref "X4") (pin "B30") (pinfunction "B30_B30") (pintype "passive"))
      (node (ref "X5") (pin "B30") (pinfunction "B30_B30") (pintype "passive"))
      (node (ref "X6") (pin "B30") (pinfunction "B30_B30") (pintype "passive"))
      (node (ref "X7") (pin "B30") (pinfunction "B30_B30") (pintype "passive"))
      (node (ref "X8") (pin "B30") (pinfunction "B30_B30") (pintype "passive"))
      (node (ref "X9") (pin "B30") (pinfunction "B30_B30") (pintype "passive"))
    )
    (net (code "10") (name "AN4") (class "Default")
      (node (ref "X1") (pin "A31") (pinfunction "A31_A31") (pintype "passive"))
      (node (ref "X10") (pin "A31") (pinfunction "A31_A31") (pintype "passive"))
      (node (ref "X11") (pin "A31") (pinfunction "A31_A31") (pintype "passive"))
      (node (ref "X12") (pin "A31") (pinfunction "A31_A31") (pintype "passive"))
      (node (ref "X13") (pin "A31") (pinfunction "A31_A31") (pintype "passive"))
      (node (ref "X14") (pin "A31") (pinfunction "A31_A31") (pintype "passive"))
      (node (ref "X15") (pin "A31") (pinfunction "A31_A31") (pintype "passive"))
      (node (ref "X16") (pin "A31") (pinfunction "A31_A31") (pintype "passive"))
      (node (ref "X17") (pin "A31") (pinfunction "A31_A31") (pintype "passive"))
      (node (ref "X18") (pin "A31") (pinfunction "A31_A31") (pintype "passive"))
      (node (ref "X19") (pin "A31") (pinfunction "A31_A31") (pintype "passive"))
      (node (ref "X2") (pin "A31") (pinfunction "A31_A31") (pintype "passive"))
      (node (ref "X20") (pin "A31") (pinfunction "A31_A31") (pintype "passive"))
      (node (ref "X3") (pin "A31") (pinfunction "A31_A31") (pintype "passive"))
      (node (ref "X4") (pin "A31") (pinfunction "A31_A31") (pintype "passive"))
      (node (ref "X5") (pin "A31") (pinfunction "A31_A31") (pintype "passive"))
      (node (ref "X6") (pin "A31") (pinfunction "A31_A31") (pintype "passive"))
      (node (ref "X7") (pin "A31") (pinfunction "A31_A31") (pintype "passive"))
      (node (ref "X8") (pin "A31") (pinfunction "A31_A31") (pintype "passive"))
      (node (ref "X9") (pin "A31") (pinfunction "A31_A31") (pintype "passive"))
    )
    (net (code "11") (name "AN5") (class "Default")
      (node (ref "X1") (pin "B31") (pinfunction "B31_B31") (pintype "passive"))
      (node (ref "X10") (pin "B31") (pinfunction "B31_B31") (pintype "passive"))
      (node (ref "X11") (pin "B31") (pinfunction "B31_B31") (pintype "passive"))
      (node (ref "X12") (pin "B31") (pinfunction "B31_B31") (pintype "passive"))
      (node (ref "X13") (pin "B31") (pinfunction "B31_B31") (pintype "passive"))
      (node (ref "X14") (pin "B31") (pinfunction "B31_B31") (pintype "passive"))
      (node (ref "X15") (pin "B31") (pinfunction "B31_B31") (pintype "passive"))
      (node (ref "X16") (pin "B31") (pinfunction "B31_B31") (pintype "passive"))
      (node (ref "X17") (pin "B31") (pinfunction "B31_B31") (pintype "passive"))
      (node (ref "X18") (pin "B31") (pinfunction "B31_B31") (pintype "passive"))
      (node (ref "X19") (pin "B31") (pinfunction "B31_B31") (pintype "passive"))
      (node (ref "X2") (pin "B31") (pinfunction "B31_B31") (pintype "passive"))
      (node (ref "X20") (pin "B31") (pinfunction "B31_B31") (pintype "passive"))
      (node (ref "X3") (pin "B31") (pinfunction "B31_B31") (pintype "passive"))
      (node (ref "X4") (pin "B31") (pinfunction "B31_B31") (pintype "passive"))
      (node (ref "X5") (pin "B31") (pinfunction "B31_B31") (pintype "passive"))
      (node (ref "X6") (pin "B31") (pinfunction "B31_B31") (pintype "passive"))
      (node (ref "X7") (pin "B31") (pinfunction "B31_B31") (pintype "passive"))
      (node (ref "X8") (pin "B31") (pinfunction "B31_B31") (pintype "passive"))
      (node (ref "X9") (pin "B31") (pinfunction "B31_B31") (pintype "passive"))
    )
    (net (code "12") (name "GND") (class "Default")
      (node (ref "SJ1") (pin "2") (pinfunction "2_2") (pintype "passive"))
      (node (ref "X1") (pin "A2") (pinfunction "A2_A2") (pintype "passive"))
      (node (ref "X1") (pin "A26") (pinfunction "A26_A26") (pintype "passive"))
      (node (ref "X1") (pin "A3") (pinfunction "A3_A3") (pintype "passive"))
      (node (ref "X1") (pin "B19") (pinfunction "B19_B19") (pintype "passive"))
      (node (ref "X1") (pin "B2") (pinfunction "B2_B2") (pintype "passive"))
      (node (ref "X1") (pin "B20") (pinfunction "B20_B20") (pintype "passive"))
      (node (ref "X1") (pin "B21") (pinfunction "B21_B21") (pintype "passive"))
      (node (ref "X1") (pin "B22") (pinfunction "B22_B22") (pintype "passive"))
      (node (ref "X1") (pin "B23") (pinfunction "B23_B23") (pintype "passive"))
      (node (ref "X1") (pin "B24") (pinfunction "B24_B24") (pintype "passive"))
      (node (ref "X1") (pin "B25") (pinfunction "B25_B25") (pintype "passive"))
      (node (ref "X1") (pin "B26") (pinfunction "B26_B26") (pintype "passive"))
      (node (ref "X1") (pin "B3") (pinfunction "B3_B3") (pintype "passive"))
      (node (ref "X10") (pin "A2") (pinfunction "A2_A2") (pintype "passive"))
      (node (ref "X10") (pin "A26") (pinfunction "A26_A26") (pintype "passive"))
      (node (ref "X10") (pin "A3") (pinfunction "A3_A3") (pintype "passive"))
      (node (ref "X10") (pin "B19") (pinfunction "B19_B19") (pintype "passive"))
      (node (ref "X10") (pin "B2") (pinfunction "B2_B2") (pintype "passive"))
      (node (ref "X10") (pin "B20") (pinfunction "B20_B20") (pintype "passive"))
      (node (ref "X10") (pin "B21") (pinfunction "B21_B21") (pintype "passive"))
      (node (ref "X10") (pin "B22") (pinfunction "B22_B22") (pintype "passive"))
      (node (ref "X10") (pin "B23") (pinfunction "B23_B23") (pintype "passive"))
      (node (ref "X10") (pin "B24") (pinfunction "B24_B24") (pintype "passive"))
      (node (ref "X10") (pin "B25") (pinfunction "B25_B25") (pintype "passive"))
      (node (ref "X10") (pin "B26") (pinfunction "B26_B26") (pintype "passive"))
      (node (ref "X10") (pin "B3") (pinfunction "B3_B3") (pintype "passive"))
      (node (ref "X11") (pin "A2") (pinfunction "A2_A2") (pintype "passive"))
      (node (ref "X11") (pin "A26") (pinfunction "A26_A26") (pintype "passive"))
      (node (ref "X11") (pin "A3") (pinfunction "A3_A3") (pintype "passive"))
      (node (ref "X11") (pin "B19") (pinfunction "B19_B19") (pintype "passive"))
      (node (ref "X11") (pin "B2") (pinfunction "B2_B2") (pintype "passive"))
      (node (ref "X11") (pin "B20") (pinfunction "B20_B20") (pintype "passive"))
      (node (ref "X11") (pin "B21") (pinfunction "B21_B21") (pintype "passive"))
      (node (ref "X11") (pin "B22") (pinfunction "B22_B22") (pintype "passive"))
      (node (ref "X11") (pin "B23") (pinfunction "B23_B23") (pintype "passive"))
      (node (ref "X11") (pin "B24") (pinfunction "B24_B24") (pintype "passive"))
      (node (ref "X11") (pin "B25") (pinfunction "B25_B25") (pintype "passive"))
      (node (ref "X11") (pin "B26") (pinfunction "B26_B26") (pintype "passive"))
      (node (ref "X11") (pin "B3") (pinfunction "B3_B3") (pintype "passive"))
      (node (ref "X12") (pin "A2") (pinfunction "A2_A2") (pintype "passive"))
      (node (ref "X12") (pin "A26") (pinfunction "A26_A26") (pintype "passive"))
      (node (ref "X12") (pin "A3") (pinfunction "A3_A3") (pintype "passive"))
      (node (ref "X12") (pin "B19") (pinfunction "B19_B19") (pintype "passive"))
      (node (ref "X12") (pin "B2") (pinfunction "B2_B2") (pintype "passive"))
      (node (ref "X12") (pin "B20") (pinfunction "B20_B20") (pintype "passive"))
      (node (ref "X12") (pin "B21") (pinfunction "B21_B21") (pintype "passive"))
      (node (ref "X12") (pin "B22") (pinfunction "B22_B22") (pintype "passive"))
      (node (ref "X12") (pin "B23") (pinfunction "B23_B23") (pintype "passive"))
      (node (ref "X12") (pin "B24") (pinfunction "B24_B24") (pintype "passive"))
      (node (ref "X12") (pin "B25") (pinfunction "B25_B25") (pintype "passive"))
      (node (ref "X12") (pin "B26") (pinfunction "B26_B26") (pintype "passive"))
      (node (ref "X12") (pin "B3") (pinfunction "B3_B3") (pintype "passive"))
      (node (ref "X13") (pin "A2") (pinfunction "A2_A2") (pintype "passive"))
      (node (ref "X13") (pin "A26") (pinfunction "A26_A26") (pintype "passive"))
      (node (ref "X13") (pin "A3") (pinfunction "A3_A3") (pintype "passive"))
      (node (ref "X13") (pin "B19") (pinfunction "B19_B19") (pintype "passive"))
      (node (ref "X13") (pin "B2") (pinfunction "B2_B2") (pintype "passive"))
      (node (ref "X13") (pin "B20") (pinfunction "B20_B20") (pintype "passive"))
      (node (ref "X13") (pin "B21") (pinfunction "B21_B21") (pintype "passive"))
      (node (ref "X13") (pin "B22") (pinfunction "B22_B22") (pintype "passive"))
      (node (ref "X13") (pin "B23") (pinfunction "B23_B23") (pintype "passive"))
      (node (ref "X13") (pin "B24") (pinfunction "B24_B24") (pintype "passive"))
      (node (ref "X13") (pin "B25") (pinfunction "B25_B25") (pintype "passive"))
      (node (ref "X13") (pin "B26") (pinfunction "B26_B26") (pintype "passive"))
      (node (ref "X13") (pin "B3") (pinfunction "B3_B3") (pintype "passive"))
      (node (ref "X14") (pin "A2") (pinfunction "A2_A2") (pintype "passive"))
      (node (ref "X14") (pin "A26") (pinfunction "A26_A26") (pintype "passive"))
      (node (ref "X14") (pin "A3") (pinfunction "A3_A3") (pintype "passive"))
      (node (ref "X14") (pin "B19") (pinfunction "B19_B19") (pintype "passive"))
      (node (ref "X14") (pin "B2") (pinfunction "B2_B2") (pintype "passive"))
      (node (ref "X14") (pin "B20") (pinfunction "B20_B20") (pintype "passive"))
      (node (ref "X14") (pin "B21") (pinfunction "B21_B21") (pintype "passive"))
      (node (ref "X14") (pin "B22") (pinfunction "B22_B22") (pintype "passive"))
      (node (ref "X14") (pin "B23") (pinfunction "B23_B23") (pintype "passive"))
      (node (ref "X14") (pin "B24") (pinfunction "B24_B24") (pintype "passive"))
      (node (ref "X14") (pin "B25") (pinfunction "B25_B25") (pintype "passive"))
      (node (ref "X14") (pin "B26") (pinfunction "B26_B26") (pintype "passive"))
      (node (ref "X14") (pin "B3") (pinfunction "B3_B3") (pintype "passive"))
      (node (ref "X15") (pin "A2") (pinfunction "A2_A2") (pintype "passive"))
      (node (ref "X15") (pin "A26") (pinfunction "A26_A26") (pintype "passive"))
      (node (ref "X15") (pin "A3") (pinfunction "A3_A3") (pintype "passive"))
      (node (ref "X15") (pin "B19") (pinfunction "B19_B19") (pintype "passive"))
      (node (ref "X15") (pin "B2") (pinfunction "B2_B2") (pintype "passive"))
      (node (ref "X15") (pin "B20") (pinfunction "B20_B20") (pintype "passive"))
      (node (ref "X15") (pin "B21") (pinfunction "B21_B21") (pintype "passive"))
      (node (ref "X15") (pin "B22") (pinfunction "B22_B22") (pintype "passive"))
      (node (ref "X15") (pin "B23") (pinfunction "B23_B23") (pintype "passive"))
      (node (ref "X15") (pin "B24") (pinfunction "B24_B24") (pintype "passive"))
      (node (ref "X15") (pin "B25") (pinfunction "B25_B25") (pintype "passive"))
      (node (ref "X15") (pin "B26") (pinfunction "B26_B26") (pintype "passive"))
      (node (ref "X15") (pin "B3") (pinfunction "B3_B3") (pintype "passive"))
      (node (ref "X16") (pin "A2") (pinfunction "A2_A2") (pintype "passive"))
      (node (ref "X16") (pin "A26") (pinfunction "A26_A26") (pintype "passive"))
      (node (ref "X16") (pin "A3") (pinfunction "A3_A3") (pintype "passive"))
      (node (ref "X16") (pin "B19") (pinfunction "B19_B19") (pintype "passive"))
      (node (ref "X16") (pin "B2") (pinfunction "B2_B2") (pintype "passive"))
      (node (ref "X16") (pin "B20") (pinfunction "B20_B20") (pintype "passive"))
      (node (ref "X16") (pin "B21") (pinfunction "B21_B21") (pintype "passive"))
      (node (ref "X16") (pin "B22") (pinfunction "B22_B22") (pintype "passive"))
      (node (ref "X16") (pin "B23") (pinfunction "B23_B23") (pintype "passive"))
      (node (ref "X16") (pin "B24") (pinfunction "B24_B24") (pintype "passive"))
      (node (ref "X16") (pin "B25") (pinfunction "B25_B25") (pintype "passive"))
      (node (ref "X16") (pin "B26") (pinfunction "B26_B26") (pintype "passive"))
      (node (ref "X16") (pin "B3") (pinfunction "B3_B3") (pintype "passive"))
      (node (ref "X17") (pin "A2") (pinfunction "A2_A2") (pintype "passive"))
      (node (ref "X17") (pin "A26") (pinfunction "A26_A26") (pintype "passive"))
      (node (ref "X17") (pin "A3") (pinfunction "A3_A3") (pintype "passive"))
      (node (ref "X17") (pin "B19") (pinfunction "B19_B19") (pintype "passive"))
      (node (ref "X17") (pin "B2") (pinfunction "B2_B2") (pintype "passive"))
      (node (ref "X17") (pin "B20") (pinfunction "B20_B20") (pintype "passive"))
      (node (ref "X17") (pin "B21") (pinfunction "B21_B21") (pintype "passive"))
      (node (ref "X17") (pin "B22") (pinfunction "B22_B22") (pintype "passive"))
      (node (ref "X17") (pin "B23") (pinfunction "B23_B23") (pintype "passive"))
      (node (ref "X17") (pin "B24") (pinfunction "B24_B24") (pintype "passive"))
      (node (ref "X17") (pin "B25") (pinfunction "B25_B25") (pintype "passive"))
      (node (ref "X17") (pin "B26") (pinfunction "B26_B26") (pintype "passive"))
      (node (ref "X17") (pin "B3") (pinfunction "B3_B3") (pintype "passive"))
      (node (ref "X18") (pin "A2") (pinfunction "A2_A2") (pintype "passive"))
      (node (ref "X18") (pin "A26") (pinfunction "A26_A26") (pintype "passive"))
      (node (ref "X18") (pin "A3") (pinfunction "A3_A3") (pintype "passive"))
      (node (ref "X18") (pin "B19") (pinfunction "B19_B19") (pintype "passive"))
      (node (ref "X18") (pin "B2") (pinfunction "B2_B2") (pintype "passive"))
      (node (ref "X18") (pin "B20") (pinfunction "B20_B20") (pintype "passive"))
      (node (ref "X18") (pin "B21") (pinfunction "B21_B21") (pintype "passive"))
      (node (ref "X18") (pin "B22") (pinfunction "B22_B22") (pintype "passive"))
      (node (ref "X18") (pin "B23") (pinfunction "B23_B23") (pintype "passive"))
      (node (ref "X18") (pin "B24") (pinfunction "B24_B24") (pintype "passive"))
      (node (ref "X18") (pin "B25") (pinfunction "B25_B25") (pintype "passive"))
      (node (ref "X18") (pin "B26") (pinfunction "B26_B26") (pintype "passive"))
      (node (ref "X18") (pin "B3") (pinfunction "B3_B3") (pintype "passive"))
      (node (ref "X19") (pin "A2") (pinfunction "A2_A2") (pintype "passive"))
      (node (ref "X19") (pin "A26") (pinfunction "A26_A26") (pintype "passive"))
      (node (ref "X19") (pin "A3") (pinfunction "A3_A3") (pintype "passive"))
      (node (ref "X19") (pin "B19") (pinfunction "B19_B19") (pintype "passive"))
      (node (ref "X19") (pin "B2") (pinfunction "B2_B2") (pintype "passive"))
      (node (ref "X19") (pin "B20") (pinfunction "B20_B20") (pintype "passive"))
      (node (ref "X19") (pin "B21") (pinfunction "B21_B21") (pintype "passive"))
      (node (ref "X19") (pin "B22") (pinfunction "B22_B22") (pintype "passive"))
      (node (ref "X19") (pin "B23") (pinfunction "B23_B23") (pintype "passive"))
      (node (ref "X19") (pin "B24") (pinfunction "B24_B24") (pintype "passive"))
      (node (ref "X19") (pin "B25") (pinfunction "B25_B25") (pintype "passive"))
      (node (ref "X19") (pin "B26") (pinfunction "B26_B26") (pintype "passive"))
      (node (ref "X19") (pin "B3") (pinfunction "B3_B3") (pintype "passive"))
      (node (ref "X2") (pin "A2") (pinfunction "A2_A2") (pintype "passive"))
      (node (ref "X2") (pin "A26") (pinfunction "A26_A26") (pintype "passive"))
      (node (ref "X2") (pin "A3") (pinfunction "A3_A3") (pintype "passive"))
      (node (ref "X2") (pin "B19") (pinfunction "B19_B19") (pintype "passive"))
      (node (ref "X2") (pin "B2") (pinfunction "B2_B2") (pintype "passive"))
      (node (ref "X2") (pin "B20") (pinfunction "B20_B20") (pintype "passive"))
      (node (ref "X2") (pin "B21") (pinfunction "B21_B21") (pintype "passive"))
      (node (ref "X2") (pin "B22") (pinfunction "B22_B22") (pintype "passive"))
      (node (ref "X2") (pin "B23") (pinfunction "B23_B23") (pintype "passive"))
      (node (ref "X2") (pin "B24") (pinfunction "B24_B24") (pintype "passive"))
      (node (ref "X2") (pin "B25") (pinfunction "B25_B25") (pintype "passive"))
      (node (ref "X2") (pin "B26") (pinfunction "B26_B26") (pintype "passive"))
      (node (ref "X2") (pin "B3") (pinfunction "B3_B3") (pintype "passive"))
      (node (ref "X20") (pin "A2") (pinfunction "A2_A2") (pintype "passive"))
      (node (ref "X20") (pin "A26") (pinfunction "A26_A26") (pintype "passive"))
      (node (ref "X20") (pin "A3") (pinfunction "A3_A3") (pintype "passive"))
      (node (ref "X20") (pin "B19") (pinfunction "B19_B19") (pintype "passive"))
      (node (ref "X20") (pin "B2") (pinfunction "B2_B2") (pintype "passive"))
      (node (ref "X20") (pin "B20") (pinfunction "B20_B20") (pintype "passive"))
      (node (ref "X20") (pin "B21") (pinfunction "B21_B21") (pintype "passive"))
      (node (ref "X20") (pin "B22") (pinfunction "B22_B22") (pintype "passive"))
      (node (ref "X20") (pin "B23") (pinfunction "B23_B23") (pintype "passive"))
      (node (ref "X20") (pin "B24") (pinfunction "B24_B24") (pintype "passive"))
      (node (ref "X20") (pin "B25") (pinfunction "B25_B25") (pintype "passive"))
      (node (ref "X20") (pin "B26") (pinfunction "B26_B26") (pintype "passive"))
      (node (ref "X20") (pin "B3") (pinfunction "B3_B3") (pintype "passive"))
      (node (ref "X3") (pin "A2") (pinfunction "A2_A2") (pintype "passive"))
      (node (ref "X3") (pin "A26") (pinfunction "A26_A26") (pintype "passive"))
      (node (ref "X3") (pin "A3") (pinfunction "A3_A3") (pintype "passive"))
      (node (ref "X3") (pin "B19") (pinfunction "B19_B19") (pintype "passive"))
      (node (ref "X3") (pin "B2") (pinfunction "B2_B2") (pintype "passive"))
      (node (ref "X3") (pin "B20") (pinfunction "B20_B20") (pintype "passive"))
      (node (ref "X3") (pin "B21") (pinfunction "B21_B21") (pintype "passive"))
      (node (ref "X3") (pin "B22") (pinfunction "B22_B22") (pintype "passive"))
      (node (ref "X3") (pin "B23") (pinfunction "B23_B23") (pintype "passive"))
      (node (ref "X3") (pin "B24") (pinfunction "B24_B24") (pintype "passive"))
      (node (ref "X3") (pin "B25") (pinfunction "B25_B25") (pintype "passive"))
      (node (ref "X3") (pin "B26") (pinfunction "B26_B26") (pintype "passive"))
      (node (ref "X3") (pin "B3") (pinfunction "B3_B3") (pintype "passive"))
      (node (ref "X4") (pin "A2") (pinfunction "A2_A2") (pintype "passive"))
      (node (ref "X4") (pin "A26") (pinfunction "A26_A26") (pintype "passive"))
      (node (ref "X4") (pin "A3") (pinfunction "A3_A3") (pintype "passive"))
      (node (ref "X4") (pin "B19") (pinfunction "B19_B19") (pintype "passive"))
      (node (ref "X4") (pin "B2") (pinfunction "B2_B2") (pintype "passive"))
      (node (ref "X4") (pin "B20") (pinfunction "B20_B20") (pintype "passive"))
      (node (ref "X4") (pin "B21") (pinfunction "B21_B21") (pintype "passive"))
      (node (ref "X4") (pin "B22") (pinfunction "B22_B22") (pintype "passive"))
      (node (ref "X4") (pin "B23") (pinfunction "B23_B23") (pintype "passive"))
      (node (ref "X4") (pin "B24") (pinfunction "B24_B24") (pintype "passive"))
      (node (ref "X4") (pin "B25") (pinfunction "B25_B25") (pintype "passive"))
      (node (ref "X4") (pin "B26") (pinfunction "B26_B26") (pintype "passive"))
      (node (ref "X4") (pin "B3") (pinfunction "B3_B3") (pintype "passive"))
      (node (ref "X5") (pin "A2") (pinfunction "A2_A2") (pintype "passive"))
      (node (ref "X5") (pin "A26") (pinfunction "A26_A26") (pintype "passive"))
      (node (ref "X5") (pin "A3") (pinfunction "A3_A3") (pintype "passive"))
      (node (ref "X5") (pin "B19") (pinfunction "B19_B19") (pintype "passive"))
      (node (ref "X5") (pin "B2") (pinfunction "B2_B2") (pintype "passive"))
      (node (ref "X5") (pin "B20") (pinfunction "B20_B20") (pintype "passive"))
      (node (ref "X5") (pin "B21") (pinfunction "B21_B21") (pintype "passive"))
      (node (ref "X5") (pin "B22") (pinfunction "B22_B22") (pintype "passive"))
      (node (ref "X5") (pin "B23") (pinfunction "B23_B23") (pintype "passive"))
      (node (ref "X5") (pin "B24") (pinfunction "B24_B24") (pintype "passive"))
      (node (ref "X5") (pin "B25") (pinfunction "B25_B25") (pintype "passive"))
      (node (ref "X5") (pin "B26") (pinfunction "B26_B26") (pintype "passive"))
      (node (ref "X5") (pin "B3") (pinfunction "B3_B3") (pintype "passive"))
      (node (ref "X6") (pin "A2") (pinfunction "A2_A2") (pintype "passive"))
      (node (ref "X6") (pin "A26") (pinfunction "A26_A26") (pintype "passive"))
      (node (ref "X6") (pin "A3") (pinfunction "A3_A3") (pintype "passive"))
      (node (ref "X6") (pin "B19") (pinfunction "B19_B19") (pintype "passive"))
      (node (ref "X6") (pin "B2") (pinfunction "B2_B2") (pintype "passive"))
      (node (ref "X6") (pin "B20") (pinfunction "B20_B20") (pintype "passive"))
      (node (ref "X6") (pin "B21") (pinfunction "B21_B21") (pintype "passive"))
      (node (ref "X6") (pin "B22") (pinfunction "B22_B22") (pintype "passive"))
      (node (ref "X6") (pin "B23") (pinfunction "B23_B23") (pintype "passive"))
      (node (ref "X6") (pin "B24") (pinfunction "B24_B24") (pintype "passive"))
      (node (ref "X6") (pin "B25") (pinfunction "B25_B25") (pintype "passive"))
      (node (ref "X6") (pin "B26") (pinfunction "B26_B26") (pintype "passive"))
      (node (ref "X6") (pin "B3") (pinfunction "B3_B3") (pintype "passive"))
      (node (ref "X7") (pin "A2") (pinfunction "A2_A2") (pintype "passive"))
      (node (ref "X7") (pin "A26") (pinfunction "A26_A26") (pintype "passive"))
      (node (ref "X7") (pin "A3") (pinfunction "A3_A3") (pintype "passive"))
      (node (ref "X7") (pin "B19") (pinfunction "B19_B19") (pintype "passive"))
      (node (ref "X7") (pin "B2") (pinfunction "B2_B2") (pintype "passive"))
      (node (ref "X7") (pin "B20") (pinfunction "B20_B20") (pintype "passive"))
      (node (ref "X7") (pin "B21") (pinfunction "B21_B21") (pintype "passive"))
      (node (ref "X7") (pin "B22") (pinfunction "B22_B22") (pintype "passive"))
      (node (ref "X7") (pin "B23") (pinfunction "B23_B23") (pintype "passive"))
      (node (ref "X7") (pin "B24") (pinfunction "B24_B24") (pintype "passive"))
      (node (ref "X7") (pin "B25") (pinfunction "B25_B25") (pintype "passive"))
      (node (ref "X7") (pin "B26") (pinfunction "B26_B26") (pintype "passive"))
      (node (ref "X7") (pin "B3") (pinfunction "B3_B3") (pintype "passive"))
      (node (ref "X8") (pin "A2") (pinfunction "A2_A2") (pintype "passive"))
      (node (ref "X8") (pin "A26") (pinfunction "A26_A26") (pintype "passive"))
      (node (ref "X8") (pin "A3") (pinfunction "A3_A3") (pintype "passive"))
      (node (ref "X8") (pin "B19") (pinfunction "B19_B19") (pintype "passive"))
      (node (ref "X8") (pin "B2") (pinfunction "B2_B2") (pintype "passive"))
      (node (ref "X8") (pin "B20") (pinfunction "B20_B20") (pintype "passive"))
      (node (ref "X8") (pin "B21") (pinfunction "B21_B21") (pintype "passive"))
      (node (ref "X8") (pin "B22") (pinfunction "B22_B22") (pintype "passive"))
      (node (ref "X8") (pin "B23") (pinfunction "B23_B23") (pintype "passive"))
      (node (ref "X8") (pin "B24") (pinfunction "B24_B24") (pintype "passive"))
      (node (ref "X8") (pin "B25") (pinfunction "B25_B25") (pintype "passive"))
      (node (ref "X8") (pin "B26") (pinfunction "B26_B26") (pintype "passive"))
      (node (ref "X8") (pin "B3") (pinfunction "B3_B3") (pintype "passive"))
      (node (ref "X9") (pin "A2") (pinfunction "A2_A2") (pintype "passive"))
      (node (ref "X9") (pin "A26") (pinfunction "A26_A26") (pintype "passive"))
      (node (ref "X9") (pin "A3") (pinfunction "A3_A3") (pintype "passive"))
      (node (ref "X9") (pin "B19") (pinfunction "B19_B19") (pintype "passive"))
      (node (ref "X9") (pin "B2") (pinfunction "B2_B2") (pintype "passive"))
      (node (ref "X9") (pin "B20") (pinfunction "B20_B20") (pintype "passive"))
      (node (ref "X9") (pin "B21") (pinfunction "B21_B21") (pintype "passive"))
      (node (ref "X9") (pin "B22") (pinfunction "B22_B22") (pintype "passive"))
      (node (ref "X9") (pin "B23") (pinfunction "B23_B23") (pintype "passive"))
      (node (ref "X9") (pin "B24") (pinfunction "B24_B24") (pintype "passive"))
      (node (ref "X9") (pin "B25") (pinfunction "B25_B25") (pintype "passive"))
      (node (ref "X9") (pin "B26") (pinfunction "B26_B26") (pintype "passive"))
      (node (ref "X9") (pin "B3") (pinfunction "B3_B3") (pintype "passive"))
    )
    (net (code "13") (name "GPIO0") (class "Default")
      (node (ref "X1") (pin "A5") (pinfunction "A5_A5") (pintype "passive"))
      (node (ref "X10") (pin "A5") (pinfunction "A5_A5") (pintype "passive"))
      (node (ref "X11") (pin "A5") (pinfunction "A5_A5") (pintype "passive"))
      (node (ref "X12") (pin "A5") (pinfunction "A5_A5") (pintype "passive"))
      (node (ref "X13") (pin "A5") (pinfunction "A5_A5") (pintype "passive"))
      (node (ref "X14") (pin "A5") (pinfunction "A5_A5") (pintype "passive"))
      (node (ref "X15") (pin "A5") (pinfunction "A5_A5") (pintype "passive"))
      (node (ref "X16") (pin "A5") (pinfunction "A5_A5") (pintype "passive"))
      (node (ref "X17") (pin "A5") (pinfunction "A5_A5") (pintype "passive"))
      (node (ref "X18") (pin "A5") (pinfunction "A5_A5") (pintype "passive"))
      (node (ref "X19") (pin "A5") (pinfunction "A5_A5") (pintype "passive"))
      (node (ref "X2") (pin "A5") (pinfunction "A5_A5") (pintype "passive"))
      (node (ref "X20") (pin "A5") (pinfunction "A5_A5") (pintype "passive"))
      (node (ref "X3") (pin "A5") (pinfunction "A5_A5") (pintype "passive"))
      (node (ref "X4") (pin "A5") (pinfunction "A5_A5") (pintype "passive"))
      (node (ref "X5") (pin "A5") (pinfunction "A5_A5") (pintype "passive"))
      (node (ref "X6") (pin "A5") (pinfunction "A5_A5") (pintype "passive"))
      (node (ref "X7") (pin "A5") (pinfunction "A5_A5") (pintype "passive"))
      (node (ref "X8") (pin "A5") (pinfunction "A5_A5") (pintype "passive"))
      (node (ref "X9") (pin "A5") (pinfunction "A5_A5") (pintype "passive"))
    )
    (net (code "14") (name "GPIO1") (class "Default")
      (node (ref "X1") (pin "B5") (pinfunction "B5_B5") (pintype "passive"))
      (node (ref "X10") (pin "B5") (pinfunction "B5_B5") (pintype "passive"))
      (node (ref "X11") (pin "B5") (pinfunction "B5_B5") (pintype "passive"))
      (node (ref "X12") (pin "B5") (pinfunction "B5_B5") (pintype "passive"))
      (node (ref "X13") (pin "B5") (pinfunction "B5_B5") (pintype "passive"))
      (node (ref "X14") (pin "B5") (pinfunction "B5_B5") (pintype "passive"))
      (node (ref "X15") (pin "B5") (pinfunction "B5_B5") (pintype "passive"))
      (node (ref "X16") (pin "B5") (pinfunction "B5_B5") (pintype "passive"))
      (node (ref "X17") (pin "B5") (pinfunction "B5_B5") (pintype "passive"))
      (node (ref "X18") (pin "B5") (pinfunction "B5_B5") (pintype "passive"))
      (node (ref "X19") (pin "B5") (pinfunction "B5_B5") (pintype "passive"))
      (node (ref "X2") (pin "B5") (pinfunction "B5_B5") (pintype "passive"))
      (node (ref "X20") (pin "B5") (pinfunction "B5_B5") (pintype "passive"))
      (node (ref "X3") (pin "B5") (pinfunction "B5_B5") (pintype "passive"))
      (node (ref "X4") (pin "B5") (pinfunction "B5_B5") (pintype "passive"))
      (node (ref "X5") (pin "B5") (pinfunction "B5_B5") (pintype "passive"))
      (node (ref "X6") (pin "B5") (pinfunction "B5_B5") (pintype "passive"))
      (node (ref "X7") (pin "B5") (pinfunction "B5_B5") (pintype "passive"))
      (node (ref "X8") (pin "B5") (pinfunction "B5_B5") (pintype "passive"))
      (node (ref "X9") (pin "B5") (pinfunction "B5_B5") (pintype "passive"))
    )
    (net (code "15") (name "GPIO2") (class "Default")
      (node (ref "X1") (pin "A6") (pinfunction "A6_A6") (pintype "passive"))
      (node (ref "X10") (pin "A6") (pinfunction "A6_A6") (pintype "passive"))
      (node (ref "X11") (pin "A6") (pinfunction "A6_A6") (pintype "passive"))
      (node (ref "X12") (pin "A6") (pinfunction "A6_A6") (pintype "passive"))
      (node (ref "X13") (pin "A6") (pinfunction "A6_A6") (pintype "passive"))
      (node (ref "X14") (pin "A6") (pinfunction "A6_A6") (pintype "passive"))
      (node (ref "X15") (pin "A6") (pinfunction "A6_A6") (pintype "passive"))
      (node (ref "X16") (pin "A6") (pinfunction "A6_A6") (pintype "passive"))
      (node (ref "X17") (pin "A6") (pinfunction "A6_A6") (pintype "passive"))
      (node (ref "X18") (pin "A6") (pinfunction "A6_A6") (pintype "passive"))
      (node (ref "X19") (pin "A6") (pinfunction "A6_A6") (pintype "passive"))
      (node (ref "X2") (pin "A6") (pinfunction "A6_A6") (pintype "passive"))
      (node (ref "X20") (pin "A6") (pinfunction "A6_A6") (pintype "passive"))
      (node (ref "X3") (pin "A6") (pinfunction "A6_A6") (pintype "passive"))
      (node (ref "X4") (pin "A6") (pinfunction "A6_A6") (pintype "passive"))
      (node (ref "X5") (pin "A6") (pinfunction "A6_A6") (pintype "passive"))
      (node (ref "X6") (pin "A6") (pinfunction "A6_A6") (pintype "passive"))
      (node (ref "X7") (pin "A6") (pinfunction "A6_A6") (pintype "passive"))
      (node (ref "X8") (pin "A6") (pinfunction "A6_A6") (pintype "passive"))
      (node (ref "X9") (pin "A6") (pinfunction "A6_A6") (pintype "passive"))
    )
    (net (code "16") (name "GPIO3") (class "Default")
      (node (ref "X1") (pin "B6") (pinfunction "B6_B6") (pintype "passive"))
      (node (ref "X10") (pin "B6") (pinfunction "B6_B6") (pintype "passive"))
      (node (ref "X11") (pin "B6") (pinfunction "B6_B6") (pintype "passive"))
      (node (ref "X12") (pin "B6") (pinfunction "B6_B6") (pintype "passive"))
      (node (ref "X13") (pin "B6") (pinfunction "B6_B6") (pintype "passive"))
      (node (ref "X14") (pin "B6") (pinfunction "B6_B6") (pintype "passive"))
      (node (ref "X15") (pin "B6") (pinfunction "B6_B6") (pintype "passive"))
      (node (ref "X16") (pin "B6") (pinfunction "B6_B6") (pintype "passive"))
      (node (ref "X17") (pin "B6") (pinfunction "B6_B6") (pintype "passive"))
      (node (ref "X18") (pin "B6") (pinfunction "B6_B6") (pintype "passive"))
      (node (ref "X19") (pin "B6") (pinfunction "B6_B6") (pintype "passive"))
      (node (ref "X2") (pin "B6") (pinfunction "B6_B6") (pintype "passive"))
      (node (ref "X20") (pin "B6") (pinfunction "B6_B6") (pintype "passive"))
      (node (ref "X3") (pin "B6") (pinfunction "B6_B6") (pintype "passive"))
      (node (ref "X4") (pin "B6") (pinfunction "B6_B6") (pintype "passive"))
      (node (ref "X5") (pin "B6") (pinfunction "B6_B6") (pintype "passive"))
      (node (ref "X6") (pin "B6") (pinfunction "B6_B6") (pintype "passive"))
      (node (ref "X7") (pin "B6") (pinfunction "B6_B6") (pintype "passive"))
      (node (ref "X8") (pin "B6") (pinfunction "B6_B6") (pintype "passive"))
      (node (ref "X9") (pin "B6") (pinfunction "B6_B6") (pintype "passive"))
    )
    (net (code "17") (name "GPIO4") (class "Default")
      (node (ref "X1") (pin "A7") (pinfunction "A7_A7") (pintype "passive"))
      (node (ref "X10") (pin "A7") (pinfunction "A7_A7") (pintype "passive"))
      (node (ref "X11") (pin "A7") (pinfunction "A7_A7") (pintype "passive"))
      (node (ref "X12") (pin "A7") (pinfunction "A7_A7") (pintype "passive"))
      (node (ref "X13") (pin "A7") (pinfunction "A7_A7") (pintype "passive"))
      (node (ref "X14") (pin "A7") (pinfunction "A7_A7") (pintype "passive"))
      (node (ref "X15") (pin "A7") (pinfunction "A7_A7") (pintype "passive"))
      (node (ref "X16") (pin "A7") (pinfunction "A7_A7") (pintype "passive"))
      (node (ref "X17") (pin "A7") (pinfunction "A7_A7") (pintype "passive"))
      (node (ref "X18") (pin "A7") (pinfunction "A7_A7") (pintype "passive"))
      (node (ref "X19") (pin "A7") (pinfunction "A7_A7") (pintype "passive"))
      (node (ref "X2") (pin "A7") (pinfunction "A7_A7") (pintype "passive"))
      (node (ref "X20") (pin "A7") (pinfunction "A7_A7") (pintype "passive"))
      (node (ref "X3") (pin "A7") (pinfunction "A7_A7") (pintype "passive"))
      (node (ref "X4") (pin "A7") (pinfunction "A7_A7") (pintype "passive"))
      (node (ref "X5") (pin "A7") (pinfunction "A7_A7") (pintype "passive"))
      (node (ref "X6") (pin "A7") (pinfunction "A7_A7") (pintype "passive"))
      (node (ref "X7") (pin "A7") (pinfunction "A7_A7") (pintype "passive"))
      (node (ref "X8") (pin "A7") (pinfunction "A7_A7") (pintype "passive"))
      (node (ref "X9") (pin "A7") (pinfunction "A7_A7") (pintype "passive"))
    )
    (net (code "18") (name "GPIO5") (class "Default")
      (node (ref "X1") (pin "B7") (pinfunction "B7_B7") (pintype "passive"))
      (node (ref "X10") (pin "B7") (pinfunction "B7_B7") (pintype "passive"))
      (node (ref "X11") (pin "B7") (pinfunction "B7_B7") (pintype "passive"))
      (node (ref "X12") (pin "B7") (pinfunction "B7_B7") (pintype "passive"))
      (node (ref "X13") (pin "B7") (pinfunction "B7_B7") (pintype "passive"))
      (node (ref "X14") (pin "B7") (pinfunction "B7_B7") (pintype "passive"))
      (node (ref "X15") (pin "B7") (pinfunction "B7_B7") (pintype "passive"))
      (node (ref "X16") (pin "B7") (pinfunction "B7_B7") (pintype "passive"))
      (node (ref "X17") (pin "B7") (pinfunction "B7_B7") (pintype "passive"))
      (node (ref "X18") (pin "B7") (pinfunction "B7_B7") (pintype "passive"))
      (node (ref "X19") (pin "B7") (pinfunction "B7_B7") (pintype "passive"))
      (node (ref "X2") (pin "B7") (pinfunction "B7_B7") (pintype "passive"))
      (node (ref "X20") (pin "B7") (pinfunction "B7_B7") (pintype "passive"))
      (node (ref "X3") (pin "B7") (pinfunction "B7_B7") (pintype "passive"))
      (node (ref "X4") (pin "B7") (pinfunction "B7_B7") (pintype "passive"))
      (node (ref "X5") (pin "B7") (pinfunction "B7_B7") (pintype "passive"))
      (node (ref "X6") (pin "B7") (pinfunction "B7_B7") (pintype "passive"))
      (node (ref "X7") (pin "B7") (pinfunction "B7_B7") (pintype "passive"))
      (node (ref "X8") (pin "B7") (pinfunction "B7_B7") (pintype "passive"))
      (node (ref "X9") (pin "B7") (pinfunction "B7_B7") (pintype "passive"))
    )
    (net (code "19") (name "GPIO6") (class "Default")
      (node (ref "X1") (pin "A8") (pinfunction "A8_A8") (pintype "passive"))
      (node (ref "X10") (pin "A8") (pinfunction "A8_A8") (pintype "passive"))
      (node (ref "X11") (pin "A8") (pinfunction "A8_A8") (pintype "passive"))
      (node (ref "X12") (pin "A8") (pinfunction "A8_A8") (pintype "passive"))
      (node (ref "X13") (pin "A8") (pinfunction "A8_A8") (pintype "passive"))
      (node (ref "X14") (pin "A8") (pinfunction "A8_A8") (pintype "passive"))
      (node (ref "X15") (pin "A8") (pinfunction "A8_A8") (pintype "passive"))
      (node (ref "X16") (pin "A8") (pinfunction "A8_A8") (pintype "passive"))
      (node (ref "X17") (pin "A8") (pinfunction "A8_A8") (pintype "passive"))
      (node (ref "X18") (pin "A8") (pinfunction "A8_A8") (pintype "passive"))
      (node (ref "X19") (pin "A8") (pinfunction "A8_A8") (pintype "passive"))
      (node (ref "X2") (pin "A8") (pinfunction "A8_A8") (pintype "passive"))
      (node (ref "X20") (pin "A8") (pinfunction "A8_A8") (pintype "passive"))
      (node (ref "X3") (pin "A8") (pinfunction "A8_A8") (pintype "passive"))
      (node (ref "X4") (pin "A8") (pinfunction "A8_A8") (pintype "passive"))
      (node (ref "X5") (pin "A8") (pinfunction "A8_A8") (pintype "passive"))
      (node (ref "X6") (pin "A8") (pinfunction "A8_A8") (pintype "passive"))
      (node (ref "X7") (pin "A8") (pinfunction "A8_A8") (pintype "passive"))
      (node (ref "X8") (pin "A8") (pinfunction "A8_A8") (pintype "passive"))
      (node (ref "X9") (pin "A8") (pinfunction "A8_A8") (pintype "passive"))
    )
    (net (code "20") (name "GPIO7") (class "Default")
      (node (ref "X1") (pin "B8") (pinfunction "B8_B8") (pintype "passive"))
      (node (ref "X10") (pin "B8") (pinfunction "B8_B8") (pintype "passive"))
      (node (ref "X11") (pin "B8") (pinfunction "B8_B8") (pintype "passive"))
      (node (ref "X12") (pin "B8") (pinfunction "B8_B8") (pintype "passive"))
      (node (ref "X13") (pin "B8") (pinfunction "B8_B8") (pintype "passive"))
      (node (ref "X14") (pin "B8") (pinfunction "B8_B8") (pintype "passive"))
      (node (ref "X15") (pin "B8") (pinfunction "B8_B8") (pintype "passive"))
      (node (ref "X16") (pin "B8") (pinfunction "B8_B8") (pintype "passive"))
      (node (ref "X17") (pin "B8") (pinfunction "B8_B8") (pintype "passive"))
      (node (ref "X18") (pin "B8") (pinfunction "B8_B8") (pintype "passive"))
      (node (ref "X19") (pin "B8") (pinfunction "B8_B8") (pintype "passive"))
      (node (ref "X2") (pin "B8") (pinfunction "B8_B8") (pintype "passive"))
      (node (ref "X20") (pin "B8") (pinfunction "B8_B8") (pintype "passive"))
      (node (ref "X3") (pin "B8") (pinfunction "B8_B8") (pintype "passive"))
      (node (ref "X4") (pin "B8") (pinfunction "B8_B8") (pintype "passive"))
      (node (ref "X5") (pin "B8") (pinfunction "B8_B8") (pintype "passive"))
      (node (ref "X6") (pin "B8") (pinfunction "B8_B8") (pintype "passive"))
      (node (ref "X7") (pin "B8") (pinfunction "B8_B8") (pintype "passive"))
      (node (ref "X8") (pin "B8") (pinfunction "B8_B8") (pintype "passive"))
      (node (ref "X9") (pin "B8") (pinfunction "B8_B8") (pintype "passive"))
    )
    (net (code "21") (name "GPIO8") (class "Default")
      (node (ref "X1") (pin "A12") (pinfunction "A12_A12") (pintype "passive"))
      (node (ref "X10") (pin "A12") (pinfunction "A12_A12") (pintype "passive"))
      (node (ref "X11") (pin "A12") (pinfunction "A12_A12") (pintype "passive"))
      (node (ref "X12") (pin "A12") (pinfunction "A12_A12") (pintype "passive"))
      (node (ref "X13") (pin "A12") (pinfunction "A12_A12") (pintype "passive"))
      (node (ref "X14") (pin "A12") (pinfunction "A12_A12") (pintype "passive"))
      (node (ref "X15") (pin "A12") (pinfunction "A12_A12") (pintype "passive"))
      (node (ref "X16") (pin "A12") (pinfunction "A12_A12") (pintype "passive"))
      (node (ref "X17") (pin "A12") (pinfunction "A12_A12") (pintype "passive"))
      (node (ref "X18") (pin "A12") (pinfunction "A12_A12") (pintype "passive"))
      (node (ref "X19") (pin "A12") (pinfunction "A12_A12") (pintype "passive"))
      (node (ref "X2") (pin "A12") (pinfunction "A12_A12") (pintype "passive"))
      (node (ref "X20") (pin "A12") (pinfunction "A12_A12") (pintype "passive"))
      (node (ref "X3") (pin "A12") (pinfunction "A12_A12") (pintype "passive"))
      (node (ref "X4") (pin "A12") (pinfunction "A12_A12") (pintype "passive"))
      (node (ref "X5") (pin "A12") (pinfunction "A12_A12") (pintype "passive"))
      (node (ref "X6") (pin "A12") (pinfunction "A12_A12") (pintype "passive"))
      (node (ref "X7") (pin "A12") (pinfunction "A12_A12") (pintype "passive"))
      (node (ref "X8") (pin "A12") (pinfunction "A12_A12") (pintype "passive"))
      (node (ref "X9") (pin "A12") (pinfunction "A12_A12") (pintype "passive"))
    )
    (net (code "22") (name "GPIO9") (class "Default")
      (node (ref "X1") (pin "B12") (pinfunction "B12_B12") (pintype "passive"))
      (node (ref "X10") (pin "B12") (pinfunction "B12_B12") (pintype "passive"))
      (node (ref "X11") (pin "B12") (pinfunction "B12_B12") (pintype "passive"))
      (node (ref "X12") (pin "B12") (pinfunction "B12_B12") (pintype "passive"))
      (node (ref "X13") (pin "B12") (pinfunction "B12_B12") (pintype "passive"))
      (node (ref "X14") (pin "B12") (pinfunction "B12_B12") (pintype "passive"))
      (node (ref "X15") (pin "B12") (pinfunction "B12_B12") (pintype "passive"))
      (node (ref "X16") (pin "B12") (pinfunction "B12_B12") (pintype "passive"))
      (node (ref "X17") (pin "B12") (pinfunction "B12_B12") (pintype "passive"))
      (node (ref "X18") (pin "B12") (pinfunction "B12_B12") (pintype "passive"))
      (node (ref "X19") (pin "B12") (pinfunction "B12_B12") (pintype "passive"))
      (node (ref "X2") (pin "B12") (pinfunction "B12_B12") (pintype "passive"))
      (node (ref "X20") (pin "B12") (pinfunction "B12_B12") (pintype "passive"))
      (node (ref "X3") (pin "B12") (pinfunction "B12_B12") (pintype "passive"))
      (node (ref "X4") (pin "B12") (pinfunction "B12_B12") (pintype "passive"))
      (node (ref "X5") (pin "B12") (pinfunction "B12_B12") (pintype "passive"))
      (node (ref "X6") (pin "B12") (pinfunction "B12_B12") (pintype "passive"))
      (node (ref "X7") (pin "B12") (pinfunction "B12_B12") (pintype "passive"))
      (node (ref "X8") (pin "B12") (pinfunction "B12_B12") (pintype "passive"))
      (node (ref "X9") (pin "B12") (pinfunction "B12_B12") (pintype "passive"))
    )
    (net (code "23") (name "GPIO10") (class "Default")
      (node (ref "X1") (pin "A13") (pinfunction "A13_A13") (pintype "passive"))
      (node (ref "X10") (pin "A13") (pinfunction "A13_A13") (pintype "passive"))
      (node (ref "X11") (pin "A13") (pinfunction "A13_A13") (pintype "passive"))
      (node (ref "X12") (pin "A13") (pinfunction "A13_A13") (pintype "passive"))
      (node (ref "X13") (pin "A13") (pinfunction "A13_A13") (pintype "passive"))
      (node (ref "X14") (pin "A13") (pinfunction "A13_A13") (pintype "passive"))
      (node (ref "X15") (pin "A13") (pinfunction "A13_A13") (pintype "passive"))
      (node (ref "X16") (pin "A13") (pinfunction "A13_A13") (pintype "passive"))
      (node (ref "X17") (pin "A13") (pinfunction "A13_A13") (pintype "passive"))
      (node (ref "X18") (pin "A13") (pinfunction "A13_A13") (pintype "passive"))
      (node (ref "X19") (pin "A13") (pinfunction "A13_A13") (pintype "passive"))
      (node (ref "X2") (pin "A13") (pinfunction "A13_A13") (pintype "passive"))
      (node (ref "X20") (pin "A13") (pinfunction "A13_A13") (pintype "passive"))
      (node (ref "X3") (pin "A13") (pinfunction "A13_A13") (pintype "passive"))
      (node (ref "X4") (pin "A13") (pinfunction "A13_A13") (pintype "passive"))
      (node (ref "X5") (pin "A13") (pinfunction "A13_A13") (pintype "passive"))
      (node (ref "X6") (pin "A13") (pinfunction "A13_A13") (pintype "passive"))
      (node (ref "X7") (pin "A13") (pinfunction "A13_A13") (pintype "passive"))
      (node (ref "X8") (pin "A13") (pinfunction "A13_A13") (pintype "passive"))
      (node (ref "X9") (pin "A13") (pinfunction "A13_A13") (pintype "passive"))
    )
    (net (code "24") (name "GPIO11") (class "Default")
      (node (ref "X1") (pin "B13") (pinfunction "B13_B13") (pintype "passive"))
      (node (ref "X10") (pin "B13") (pinfunction "B13_B13") (pintype "passive"))
      (node (ref "X11") (pin "B13") (pinfunction "B13_B13") (pintype "passive"))
      (node (ref "X12") (pin "B13") (pinfunction "B13_B13") (pintype "passive"))
      (node (ref "X13") (pin "B13") (pinfunction "B13_B13") (pintype "passive"))
      (node (ref "X14") (pin "B13") (pinfunction "B13_B13") (pintype "passive"))
      (node (ref "X15") (pin "B13") (pinfunction "B13_B13") (pintype "passive"))
      (node (ref "X16") (pin "B13") (pinfunction "B13_B13") (pintype "passive"))
      (node (ref "X17") (pin "B13") (pinfunction "B13_B13") (pintype "passive"))
      (node (ref "X18") (pin "B13") (pinfunction "B13_B13") (pintype "passive"))
      (node (ref "X19") (pin "B13") (pinfunction "B13_B13") (pintype "passive"))
      (node (ref "X2") (pin "B13") (pinfunction "B13_B13") (pintype "passive"))
      (node (ref "X20") (pin "B13") (pinfunction "B13_B13") (pintype "passive"))
      (node (ref "X3") (pin "B13") (pinfunction "B13_B13") (pintype "passive"))
      (node (ref "X4") (pin "B13") (pinfunction "B13_B13") (pintype "passive"))
      (node (ref "X5") (pin "B13") (pinfunction "B13_B13") (pintype "passive"))
      (node (ref "X6") (pin "B13") (pinfunction "B13_B13") (pintype "passive"))
      (node (ref "X7") (pin "B13") (pinfunction "B13_B13") (pintype "passive"))
      (node (ref "X8") (pin "B13") (pinfunction "B13_B13") (pintype "passive"))
      (node (ref "X9") (pin "B13") (pinfunction "B13_B13") (pintype "passive"))
    )
    (net (code "25") (name "GPIO12") (class "Default")
      (node (ref "X1") (pin "A14") (pinfunction "A14_A14") (pintype "passive"))
      (node (ref "X10") (pin "A14") (pinfunction "A14_A14") (pintype "passive"))
      (node (ref "X11") (pin "A14") (pinfunction "A14_A14") (pintype "passive"))
      (node (ref "X12") (pin "A14") (pinfunction "A14_A14") (pintype "passive"))
      (node (ref "X13") (pin "A14") (pinfunction "A14_A14") (pintype "passive"))
      (node (ref "X14") (pin "A14") (pinfunction "A14_A14") (pintype "passive"))
      (node (ref "X15") (pin "A14") (pinfunction "A14_A14") (pintype "passive"))
      (node (ref "X16") (pin "A14") (pinfunction "A14_A14") (pintype "passive"))
      (node (ref "X17") (pin "A14") (pinfunction "A14_A14") (pintype "passive"))
      (node (ref "X18") (pin "A14") (pinfunction "A14_A14") (pintype "passive"))
      (node (ref "X19") (pin "A14") (pinfunction "A14_A14") (pintype "passive"))
      (node (ref "X2") (pin "A14") (pinfunction "A14_A14") (pintype "passive"))
      (node (ref "X20") (pin "A14") (pinfunction "A14_A14") (pintype "passive"))
      (node (ref "X3") (pin "A14") (pinfunction "A14_A14") (pintype "passive"))
      (node (ref "X4") (pin "A14") (pinfunction "A14_A14") (pintype "passive"))
      (node (ref "X5") (pin "A14") (pinfunction "A14_A14") (pintype "passive"))
      (node (ref "X6") (pin "A14") (pinfunction "A14_A14") (pintype "passive"))
      (node (ref "X7") (pin "A14") (pinfunction "A14_A14") (pintype "passive"))
      (node (ref "X8") (pin "A14") (pinfunction "A14_A14") (pintype "passive"))
      (node (ref "X9") (pin "A14") (pinfunction "A14_A14") (pintype "passive"))
    )
    (net (code "26") (name "GPIO13") (class "Default")
      (node (ref "X1") (pin "B14") (pinfunction "B14_B14") (pintype "passive"))
      (node (ref "X10") (pin "B14") (pinfunction "B14_B14") (pintype "passive"))
      (node (ref "X11") (pin "B14") (pinfunction "B14_B14") (pintype "passive"))
      (node (ref "X12") (pin "B14") (pinfunction "B14_B14") (pintype "passive"))
      (node (ref "X13") (pin "B14") (pinfunction "B14_B14") (pintype "passive"))
      (node (ref "X14") (pin "B14") (pinfunction "B14_B14") (pintype "passive"))
      (node (ref "X15") (pin "B14") (pinfunction "B14_B14") (pintype "passive"))
      (node (ref "X16") (pin "B14") (pinfunction "B14_B14") (pintype "passive"))
      (node (ref "X17") (pin "B14") (pinfunction "B14_B14") (pintype "passive"))
      (node (ref "X18") (pin "B14") (pinfunction "B14_B14") (pintype "passive"))
      (node (ref "X19") (pin "B14") (pinfunction "B14_B14") (pintype "passive"))
      (node (ref "X2") (pin "B14") (pinfunction "B14_B14") (pintype "passive"))
      (node (ref "X20") (pin "B14") (pinfunction "B14_B14") (pintype "passive"))
      (node (ref "X3") (pin "B14") (pinfunction "B14_B14") (pintype "passive"))
      (node (ref "X4") (pin "B14") (pinfunction "B14_B14") (pintype "passive"))
      (node (ref "X5") (pin "B14") (pinfunction "B14_B14") (pintype "passive"))
      (node (ref "X6") (pin "B14") (pinfunction "B14_B14") (pintype "passive"))
      (node (ref "X7") (pin "B14") (pinfunction "B14_B14") (pintype "passive"))
      (node (ref "X8") (pin "B14") (pinfunction "B14_B14") (pintype "passive"))
      (node (ref "X9") (pin "B14") (pinfunction "B14_B14") (pintype "passive"))
    )
    (net (code "27") (name "GPIO14") (class "Default")
      (node (ref "X1") (pin "A15") (pinfunction "A15_A15") (pintype "passive"))
      (node (ref "X10") (pin "A15") (pinfunction "A15_A15") (pintype "passive"))
      (node (ref "X11") (pin "A15") (pinfunction "A15_A15") (pintype "passive"))
      (node (ref "X12") (pin "A15") (pinfunction "A15_A15") (pintype "passive"))
      (node (ref "X13") (pin "A15") (pinfunction "A15_A15") (pintype "passive"))
      (node (ref "X14") (pin "A15") (pinfunction "A15_A15") (pintype "passive"))
      (node (ref "X15") (pin "A15") (pinfunction "A15_A15") (pintype "passive"))
      (node (ref "X16") (pin "A15") (pinfunction "A15_A15") (pintype "passive"))
      (node (ref "X17") (pin "A15") (pinfunction "A15_A15") (pintype "passive"))
      (node (ref "X18") (pin "A15") (pinfunction "A15_A15") (pintype "passive"))
      (node (ref "X19") (pin "A15") (pinfunction "A15_A15") (pintype "passive"))
      (node (ref "X2") (pin "A15") (pinfunction "A15_A15") (pintype "passive"))
      (node (ref "X20") (pin "A15") (pinfunction "A15_A15") (pintype "passive"))
      (node (ref "X3") (pin "A15") (pinfunction "A15_A15") (pintype "passive"))
      (node (ref "X4") (pin "A15") (pinfunction "A15_A15") (pintype "passive"))
      (node (ref "X5") (pin "A15") (pinfunction "A15_A15") (pintype "passive"))
      (node (ref "X6") (pin "A15") (pinfunction "A15_A15") (pintype "passive"))
      (node (ref "X7") (pin "A15") (pinfunction "A15_A15") (pintype "passive"))
      (node (ref "X8") (pin "A15") (pinfunction "A15_A15") (pintype "passive"))
      (node (ref "X9") (pin "A15") (pinfunction "A15_A15") (pintype "passive"))
    )
    (net (code "28") (name "GPIO15") (class "Default")
      (node (ref "X1") (pin "B15") (pinfunction "B15_B15") (pintype "passive"))
      (node (ref "X10") (pin "B15") (pinfunction "B15_B15") (pintype "passive"))
      (node (ref "X11") (pin "B15") (pinfunction "B15_B15") (pintype "passive"))
      (node (ref "X12") (pin "B15") (pinfunction "B15_B15") (pintype "passive"))
      (node (ref "X13") (pin "B15") (pinfunction "B15_B15") (pintype "passive"))
      (node (ref "X14") (pin "B15") (pinfunction "B15_B15") (pintype "passive"))
      (node (ref "X15") (pin "B15") (pinfunction "B15_B15") (pintype "passive"))
      (node (ref "X16") (pin "B15") (pinfunction "B15_B15") (pintype "passive"))
      (node (ref "X17") (pin "B15") (pinfunction "B15_B15") (pintype "passive"))
      (node (ref "X18") (pin "B15") (pinfunction "B15_B15") (pintype "passive"))
      (node (ref "X19") (pin "B15") (pinfunction "B15_B15") (pintype "passive"))
      (node (ref "X2") (pin "B15") (pinfunction "B15_B15") (pintype "passive"))
      (node (ref "X20") (pin "B15") (pinfunction "B15_B15") (pintype "passive"))
      (node (ref "X3") (pin "B15") (pinfunction "B15_B15") (pintype "passive"))
      (node (ref "X4") (pin "B15") (pinfunction "B15_B15") (pintype "passive"))
      (node (ref "X5") (pin "B15") (pinfunction "B15_B15") (pintype "passive"))
      (node (ref "X6") (pin "B15") (pinfunction "B15_B15") (pintype "passive"))
      (node (ref "X7") (pin "B15") (pinfunction "B15_B15") (pintype "passive"))
      (node (ref "X8") (pin "B15") (pinfunction "B15_B15") (pintype "passive"))
      (node (ref "X9") (pin "B15") (pinfunction "B15_B15") (pintype "passive"))
    )
    (net (code "29") (name "I2C_CLK") (class "Default")
      (node (ref "X1") (pin "A22") (pinfunction "A22_A22") (pintype "passive"))
      (node (ref "X10") (pin "A22") (pinfunction "A22_A22") (pintype "passive"))
      (node (ref "X11") (pin "A22") (pinfunction "A22_A22") (pintype "passive"))
      (node (ref "X12") (pin "A22") (pinfunction "A22_A22") (pintype "passive"))
      (node (ref "X13") (pin "A22") (pinfunction "A22_A22") (pintype "passive"))
      (node (ref "X14") (pin "A22") (pinfunction "A22_A22") (pintype "passive"))
      (node (ref "X15") (pin "A22") (pinfunction "A22_A22") (pintype "passive"))
      (node (ref "X16") (pin "A22") (pinfunction "A22_A22") (pintype "passive"))
      (node (ref "X17") (pin "A22") (pinfunction "A22_A22") (pintype "passive"))
      (node (ref "X18") (pin "A22") (pinfunction "A22_A22") (pintype "passive"))
      (node (ref "X19") (pin "A22") (pinfunction "A22_A22") (pintype "passive"))
      (node (ref "X2") (pin "A22") (pinfunction "A22_A22") (pintype "passive"))
      (node (ref "X20") (pin "A22") (pinfunction "A22_A22") (pintype "passive"))
      (node (ref "X3") (pin "A22") (pinfunction "A22_A22") (pintype "passive"))
      (node (ref "X4") (pin "A22") (pinfunction "A22_A22") (pintype "passive"))
      (node (ref "X5") (pin "A22") (pinfunction "A22_A22") (pintype "passive"))
      (node (ref "X6") (pin "A22") (pinfunction "A22_A22") (pintype "passive"))
      (node (ref "X7") (pin "A22") (pinfunction "A22_A22") (pintype "passive"))
      (node (ref "X8") (pin "A22") (pinfunction "A22_A22") (pintype "passive"))
      (node (ref "X9") (pin "A22") (pinfunction "A22_A22") (pintype "passive"))
    )
    (net (code "30") (name "I2C_DAT") (class "Default")
      (node (ref "X1") (pin "A23") (pinfunction "A23_A23") (pintype "passive"))
      (node (ref "X10") (pin "A23") (pinfunction "A23_A23") (pintype "passive"))
      (node (ref "X11") (pin "A23") (pinfunction "A23_A23") (pintype "passive"))
      (node (ref "X12") (pin "A23") (pinfunction "A23_A23") (pintype "passive"))
      (node (ref "X13") (pin "A23") (pinfunction "A23_A23") (pintype "passive"))
      (node (ref "X14") (pin "A23") (pinfunction "A23_A23") (pintype "passive"))
      (node (ref "X15") (pin "A23") (pinfunction "A23_A23") (pintype "passive"))
      (node (ref "X16") (pin "A23") (pinfunction "A23_A23") (pintype "passive"))
      (node (ref "X17") (pin "A23") (pinfunction "A23_A23") (pintype "passive"))
      (node (ref "X18") (pin "A23") (pinfunction "A23_A23") (pintype "passive"))
      (node (ref "X19") (pin "A23") (pinfunction "A23_A23") (pintype "passive"))
      (node (ref "X2") (pin "A23") (pinfunction "A23_A23") (pintype "passive"))
      (node (ref "X20") (pin "A23") (pinfunction "A23_A23") (pintype "passive"))
      (node (ref "X3") (pin "A23") (pinfunction "A23_A23") (pintype "passive"))
      (node (ref "X4") (pin "A23") (pinfunction "A23_A23") (pintype "passive"))
      (node (ref "X5") (pin "A23") (pinfunction "A23_A23") (pintype "passive"))
      (node (ref "X6") (pin "A23") (pinfunction "A23_A23") (pintype "passive"))
      (node (ref "X7") (pin "A23") (pinfunction "A23_A23") (pintype "passive"))
      (node (ref "X8") (pin "A23") (pinfunction "A23_A23") (pintype "passive"))
      (node (ref "X9") (pin "A23") (pinfunction "A23_A23") (pintype "passive"))
    )
    (net (code "31") (name "SPI_CLK") (class "Default")
      (node (ref "X1") (pin "A19") (pinfunction "A19_A19") (pintype "passive"))
      (node (ref "X10") (pin "A19") (pinfunction "A19_A19") (pintype "passive"))
      (node (ref "X11") (pin "A19") (pinfunction "A19_A19") (pintype "passive"))
      (node (ref "X12") (pin "A19") (pinfunction "A19_A19") (pintype "passive"))
      (node (ref "X13") (pin "A19") (pinfunction "A19_A19") (pintype "passive"))
      (node (ref "X14") (pin "A19") (pinfunction "A19_A19") (pintype "passive"))
      (node (ref "X15") (pin "A19") (pinfunction "A19_A19") (pintype "passive"))
      (node (ref "X16") (pin "A19") (pinfunction "A19_A19") (pintype "passive"))
      (node (ref "X17") (pin "A19") (pinfunction "A19_A19") (pintype "passive"))
      (node (ref "X18") (pin "A19") (pinfunction "A19_A19") (pintype "passive"))
      (node (ref "X19") (pin "A19") (pinfunction "A19_A19") (pintype "passive"))
      (node (ref "X2") (pin "A19") (pinfunction "A19_A19") (pintype "passive"))
      (node (ref "X20") (pin "A19") (pinfunction "A19_A19") (pintype "passive"))
      (node (ref "X3") (pin "A19") (pinfunction "A19_A19") (pintype "passive"))
      (node (ref "X4") (pin "A19") (pinfunction "A19_A19") (pintype "passive"))
      (node (ref "X5") (pin "A19") (pinfunction "A19_A19") (pintype "passive"))
      (node (ref "X6") (pin "A19") (pinfunction "A19_A19") (pintype "passive"))
      (node (ref "X7") (pin "A19") (pinfunction "A19_A19") (pintype "passive"))
      (node (ref "X8") (pin "A19") (pinfunction "A19_A19") (pintype "passive"))
      (node (ref "X9") (pin "A19") (pinfunction "A19_A19") (pintype "passive"))
    )
    (net (code "32") (name "SPI_MISO") (class "Default")
      (node (ref "X1") (pin "A21") (pinfunction "A21_A21") (pintype "passive"))
      (node (ref "X10") (pin "A21") (pinfunction "A21_A21") (pintype "passive"))
      (node (ref "X11") (pin "A21") (pinfunction "A21_A21") (pintype "passive"))
      (node (ref "X12") (pin "A21") (pinfunction "A21_A21") (pintype "passive"))
      (node (ref "X13") (pin "A21") (pinfunction "A21_A21") (pintype "passive"))
      (node (ref "X14") (pin "A21") (pinfunction "A21_A21") (pintype "passive"))
      (node (ref "X15") (pin "A21") (pinfunction "A21_A21") (pintype "passive"))
      (node (ref "X16") (pin "A21") (pinfunction "A21_A21") (pintype "passive"))
      (node (ref "X17") (pin "A21") (pinfunction "A21_A21") (pintype "passive"))
      (node (ref "X18") (pin "A21") (pinfunction "A21_A21") (pintype "passive"))
      (node (ref "X19") (pin "A21") (pinfunction "A21_A21") (pintype "passive"))
      (node (ref "X2") (pin "A21") (pinfunction "A21_A21") (pintype "passive"))
      (node (ref "X20") (pin "A21") (pinfunction "A21_A21") (pintype "passive"))
      (node (ref "X3") (pin "A21") (pinfunction "A21_A21") (pintype "passive"))
      (node (ref "X4") (pin "A21") (pinfunction "A21_A21") (pintype "passive"))
      (node (ref "X5") (pin "A21") (pinfunction "A21_A21") (pintype "passive"))
      (node (ref "X6") (pin "A21") (pinfunction "A21_A21") (pintype "passive"))
      (node (ref "X7") (pin "A21") (pinfunction "A21_A21") (pintype "passive"))
      (node (ref "X8") (pin "A21") (pinfunction "A21_A21") (pintype "passive"))
      (node (ref "X9") (pin "A21") (pinfunction "A21_A21") (pintype "passive"))
    )
    (net (code "33") (name "SPI_MOSI") (class "Default")
      (node (ref "X1") (pin "A20") (pinfunction "A20_A20") (pintype "passive"))
      (node (ref "X10") (pin "A20") (pinfunction "A20_A20") (pintype "passive"))
      (node (ref "X11") (pin "A20") (pinfunction "A20_A20") (pintype "passive"))
      (node (ref "X12") (pin "A20") (pinfunction "A20_A20") (pintype "passive"))
      (node (ref "X13") (pin "A20") (pinfunction "A20_A20") (pintype "passive"))
      (node (ref "X14") (pin "A20") (pinfunction "A20_A20") (pintype "passive"))
      (node (ref "X15") (pin "A20") (pinfunction "A20_A20") (pintype "passive"))
      (node (ref "X16") (pin "A20") (pinfunction "A20_A20") (pintype "passive"))
      (node (ref "X17") (pin "A20") (pinfunction "A20_A20") (pintype "passive"))
      (node (ref "X18") (pin "A20") (pinfunction "A20_A20") (pintype "passive"))
      (node (ref "X19") (pin "A20") (pinfunction "A20_A20") (pintype "passive"))
      (node (ref "X2") (pin "A20") (pinfunction "A20_A20") (pintype "passive"))
      (node (ref "X20") (pin "A20") (pinfunction "A20_A20") (pintype "passive"))
      (node (ref "X3") (pin "A20") (pinfunction "A20_A20") (pintype "passive"))
      (node (ref "X4") (pin "A20") (pinfunction "A20_A20") (pintype "passive"))
      (node (ref "X5") (pin "A20") (pinfunction "A20_A20") (pintype "passive"))
      (node (ref "X6") (pin "A20") (pinfunction "A20_A20") (pintype "passive"))
      (node (ref "X7") (pin "A20") (pinfunction "A20_A20") (pintype "passive"))
      (node (ref "X8") (pin "A20") (pinfunction "A20_A20") (pintype "passive"))
      (node (ref "X9") (pin "A20") (pinfunction "A20_A20") (pintype "passive"))
    )
    (net (code "34") (name "UC_RX") (class "Default")
      (node (ref "X1") (pin "A25") (pinfunction "A25_A25") (pintype "passive"))
      (node (ref "X10") (pin "A25") (pinfunction "A25_A25") (pintype "passive"))
      (node (ref "X11") (pin "A25") (pinfunction "A25_A25") (pintype "passive"))
      (node (ref "X12") (pin "A25") (pinfunction "A25_A25") (pintype "passive"))
      (node (ref "X13") (pin "A25") (pinfunction "A25_A25") (pintype "passive"))
      (node (ref "X14") (pin "A25") (pinfunction "A25_A25") (pintype "passive"))
      (node (ref "X15") (pin "A25") (pinfunction "A25_A25") (pintype "passive"))
      (node (ref "X16") (pin "A25") (pinfunction "A25_A25") (pintype "passive"))
      (node (ref "X17") (pin "A25") (pinfunction "A25_A25") (pintype "passive"))
      (node (ref "X18") (pin "A25") (pinfunction "A25_A25") (pintype "passive"))
      (node (ref "X19") (pin "A25") (pinfunction "A25_A25") (pintype "passive"))
      (node (ref "X2") (pin "A25") (pinfunction "A25_A25") (pintype "passive"))
      (node (ref "X20") (pin "A25") (pinfunction "A25_A25") (pintype "passive"))
      (node (ref "X3") (pin "A25") (pinfunction "A25_A25") (pintype "passive"))
      (node (ref "X4") (pin "A25") (pinfunction "A25_A25") (pintype "passive"))
      (node (ref "X5") (pin "A25") (pinfunction "A25_A25") (pintype "passive"))
      (node (ref "X6") (pin "A25") (pinfunction "A25_A25") (pintype "passive"))
      (node (ref "X7") (pin "A25") (pinfunction "A25_A25") (pintype "passive"))
      (node (ref "X8") (pin "A25") (pinfunction "A25_A25") (pintype "passive"))
      (node (ref "X9") (pin "A25") (pinfunction "A25_A25") (pintype "passive"))
    )
    (net (code "35") (name "UC_TX") (class "Default")
      (node (ref "X1") (pin "A24") (pinfunction "A24_A24") (pintype "passive"))
      (node (ref "X10") (pin "A24") (pinfunction "A24_A24") (pintype "passive"))
      (node (ref "X11") (pin "A24") (pinfunction "A24_A24") (pintype "passive"))
      (node (ref "X12") (pin "A24") (pinfunction "A24_A24") (pintype "passive"))
      (node (ref "X13") (pin "A24") (pinfunction "A24_A24") (pintype "passive"))
      (node (ref "X14") (pin "A24") (pinfunction "A24_A24") (pintype "passive"))
      (node (ref "X15") (pin "A24") (pinfunction "A24_A24") (pintype "passive"))
      (node (ref "X16") (pin "A24") (pinfunction "A24_A24") (pintype "passive"))
      (node (ref "X17") (pin "A24") (pinfunction "A24_A24") (pintype "passive"))
      (node (ref "X18") (pin "A24") (pinfunction "A24_A24") (pintype "passive"))
      (node (ref "X19") (pin "A24") (pinfunction "A24_A24") (pintype "passive"))
      (node (ref "X2") (pin "A24") (pinfunction "A24_A24") (pintype "passive"))
      (node (ref "X20") (pin "A24") (pinfunction "A24_A24") (pintype "passive"))
      (node (ref "X3") (pin "A24") (pinfunction "A24_A24") (pintype "passive"))
      (node (ref "X4") (pin "A24") (pinfunction "A24_A24") (pintype "passive"))
      (node (ref "X5") (pin "A24") (pinfunction "A24_A24") (pintype "passive"))
      (node (ref "X6") (pin "A24") (pinfunction "A24_A24") (pintype "passive"))
      (node (ref "X7") (pin "A24") (pinfunction "A24_A24") (pintype "passive"))
      (node (ref "X8") (pin "A24") (pinfunction "A24_A24") (pintype "passive"))
      (node (ref "X9") (pin "A24") (pinfunction "A24_A24") (pintype "passive"))
    )
  )
)
